# FFT_IFFT.net
KiCad netlist of a schematic drawn in Altium Designer
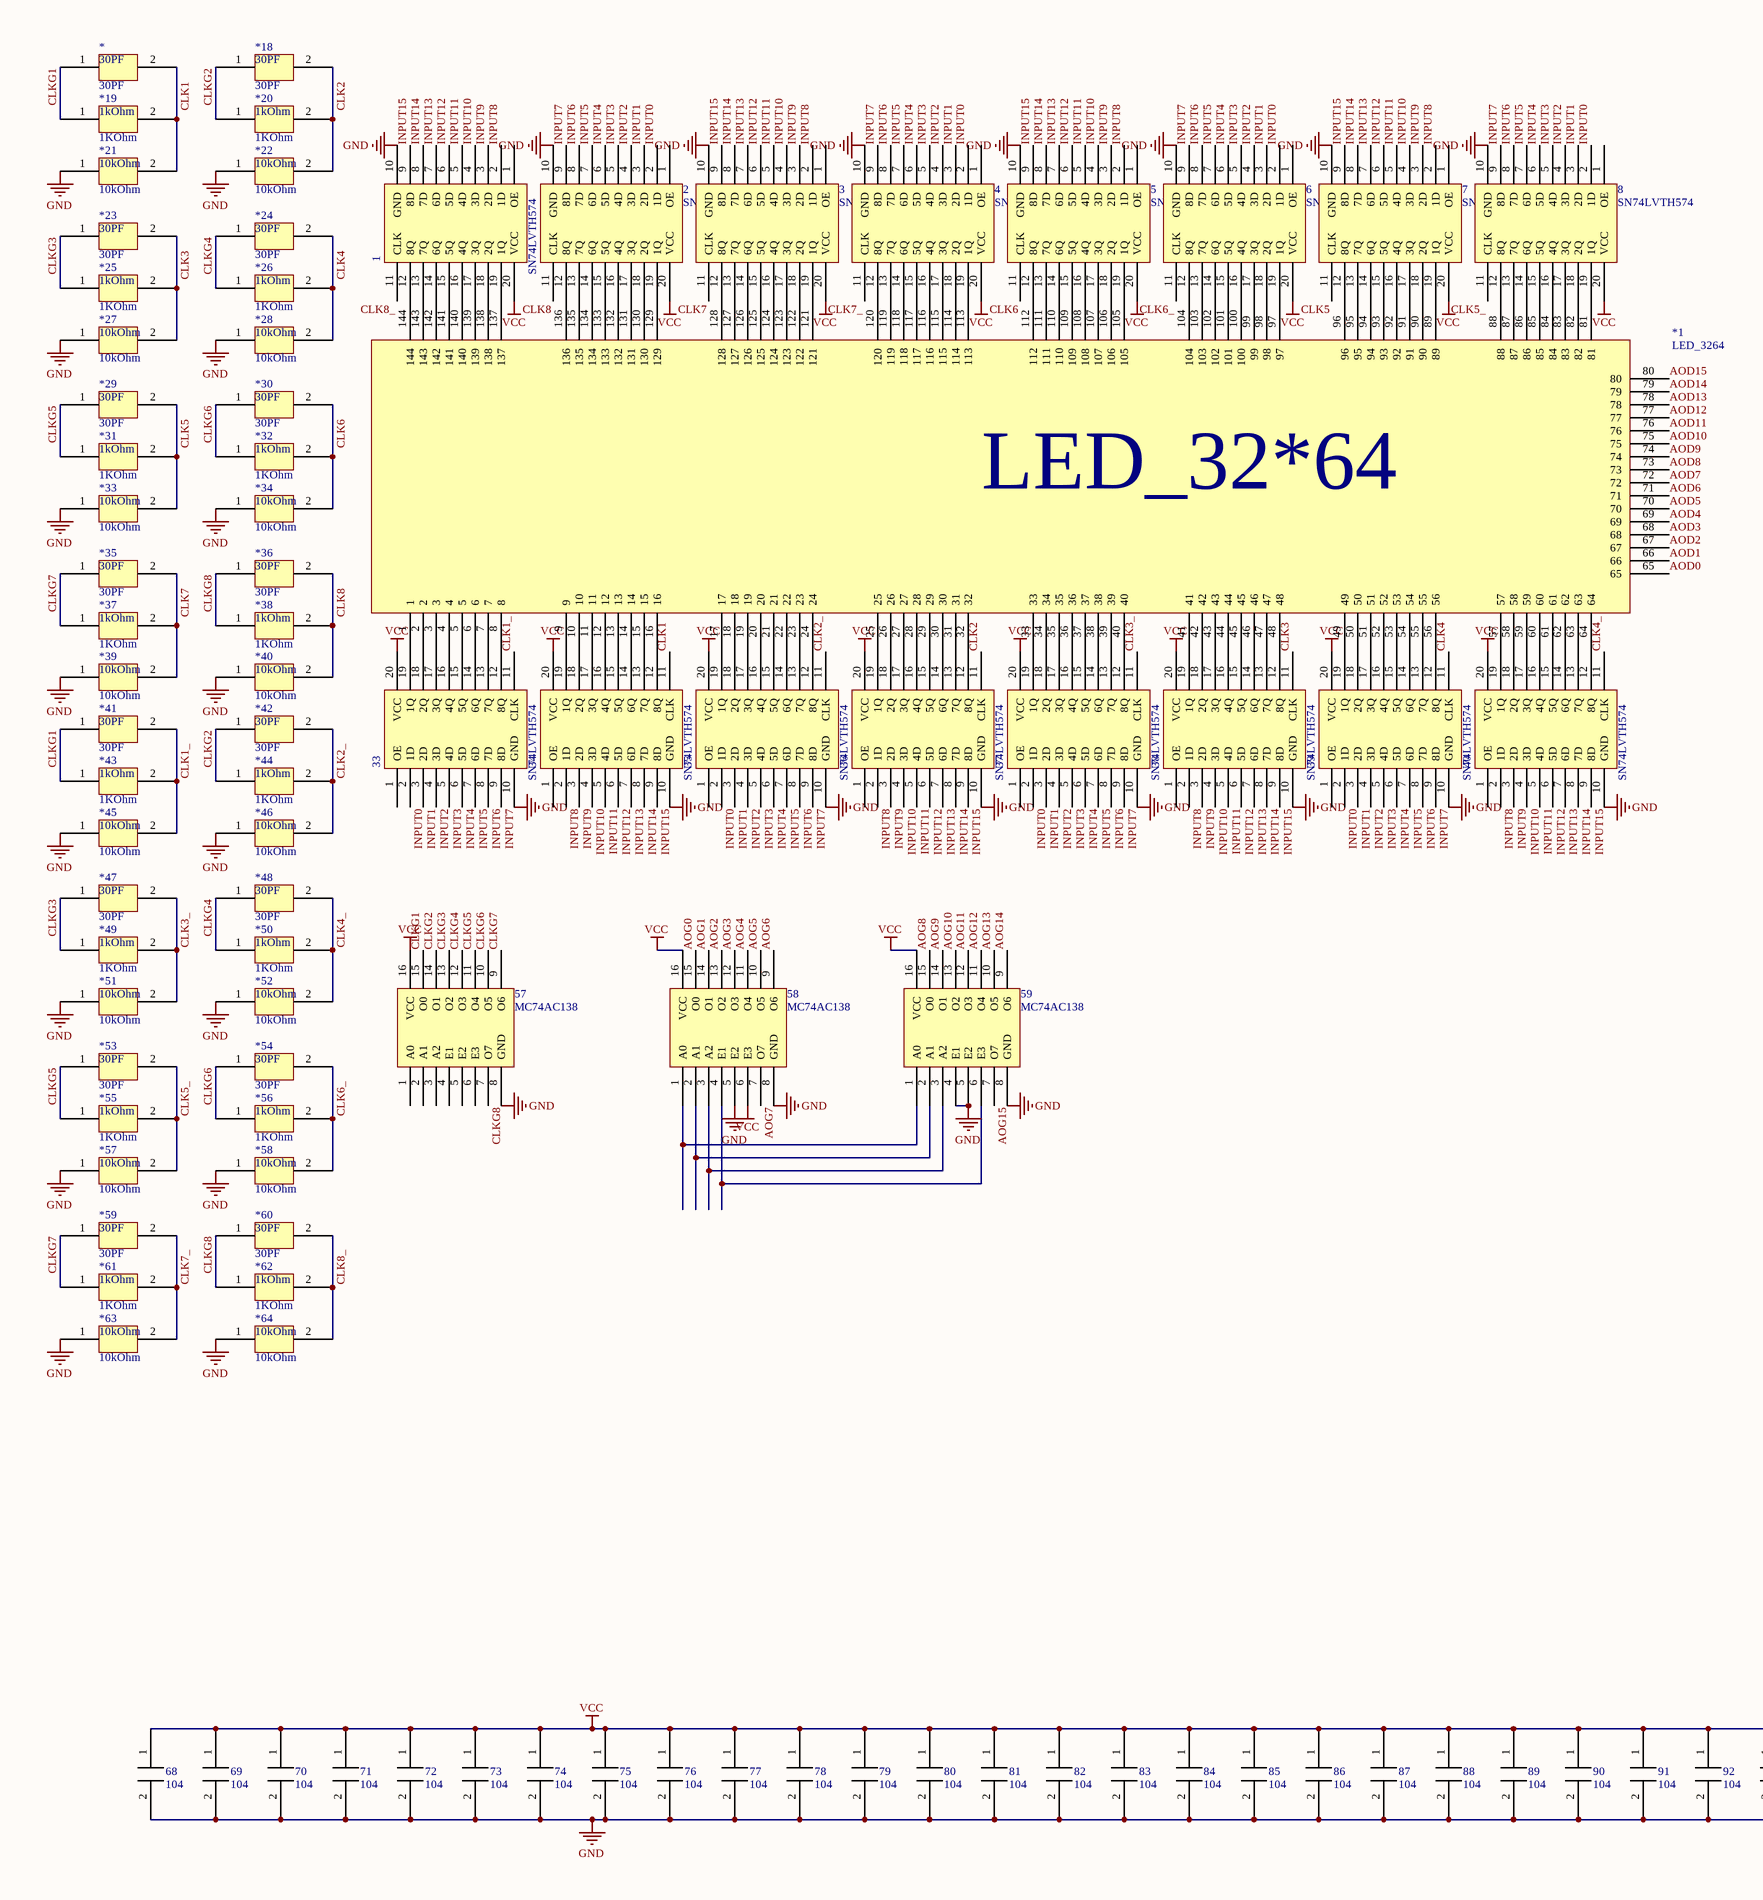
[diagram p0: FFT_IFFT.SchDoc, left]
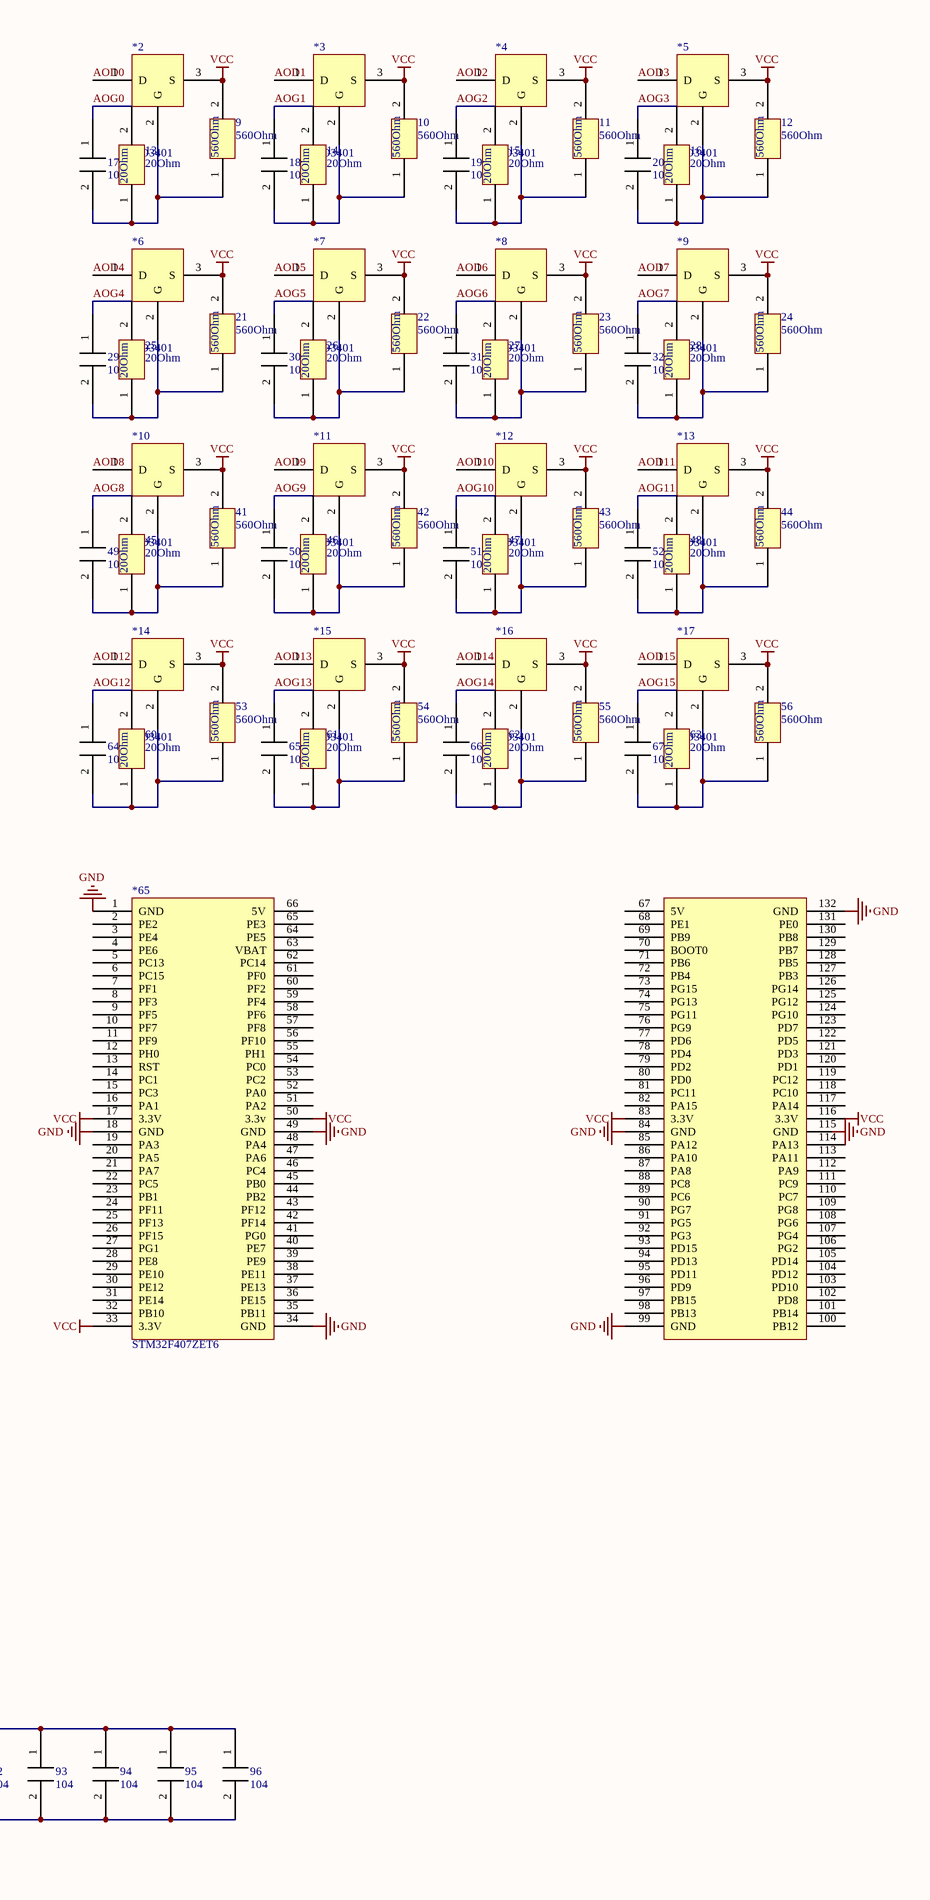
[diagram p1: FFT_IFFT.SchDoc, right]

(export (version "E")
  (design (tool "Eeschema 10.0.6"))
  (components
    (comp (ref "*") (value "30PF") (footprint "104") (libsource (lib "Schlib1") (part "30PF")))
    (comp (ref "*1") (value "LED_3264") (footprint "LED_3264") (libsource (lib "Schlib1") (part "LED_3264")))
    (comp (ref "*2") (value "AO3401") (footprint "AO3401") (libsource (lib "Schlib1") (part "AO3401")))
    (comp (ref "*3") (value "AO3401") (footprint "AO3401") (libsource (lib "Schlib1") (part "AO3401")))
    (comp (ref "*4") (value "AO3401") (footprint "AO3401") (libsource (lib "Schlib1") (part "AO3401")))
    (comp (ref "*5") (value "AO3401") (footprint "AO3401") (libsource (lib "Schlib1") (part "AO3401")))
    (comp (ref "*6") (value "AO3401") (footprint "AO3401") (libsource (lib "Schlib1") (part "AO3401")))
    (comp (ref "*7") (value "AO3401") (footprint "AO3401") (libsource (lib "Schlib1") (part "AO3401")))
    (comp (ref "*8") (value "AO3401") (footprint "AO3401") (libsource (lib "Schlib1") (part "AO3401")))
    (comp (ref "*9") (value "AO3401") (footprint "AO3401") (libsource (lib "Schlib1") (part "AO3401")))
    (comp (ref "*10") (value "AO3401") (footprint "AO3401") (libsource (lib "Schlib1") (part "AO3401")))
    (comp (ref "*11") (value "AO3401") (footprint "AO3401") (libsource (lib "Schlib1") (part "AO3401")))
    (comp (ref "*12") (value "AO3401") (footprint "AO3401") (libsource (lib "Schlib1") (part "AO3401")))
    (comp (ref "*13") (value "AO3401") (footprint "AO3401") (libsource (lib "Schlib1") (part "AO3401")))
    (comp (ref "*14") (value "AO3401") (footprint "AO3401") (libsource (lib "Schlib1") (part "AO3401")))
    (comp (ref "*15") (value "AO3401") (footprint "AO3401") (libsource (lib "Schlib1") (part "AO3401")))
    (comp (ref "*16") (value "AO3401") (footprint "AO3401") (libsource (lib "Schlib1") (part "AO3401")))
    (comp (ref "*17") (value "AO3401") (footprint "AO3401") (libsource (lib "Schlib1") (part "AO3401")))
    (comp (ref "*18") (value "30PF") (footprint "104") (libsource (lib "Schlib1") (part "30PF")))
    (comp (ref "*19") (value "1KOhm") (footprint "104") (libsource (lib "Schlib1") (part "1KOhm")))
    (comp (ref "*20") (value "1KOhm") (footprint "104") (libsource (lib "Schlib1") (part "1KOhm")))
    (comp (ref "*21") (value "10kOhm") (footprint "104") (libsource (lib "Schlib1") (part "10kOhm")))
    (comp (ref "*22") (value "10kOhm") (footprint "104") (libsource (lib "Schlib1") (part "10kOhm")))
    (comp (ref "*23") (value "30PF") (footprint "104") (libsource (lib "Schlib1") (part "30PF")))
    (comp (ref "*24") (value "30PF") (footprint "104") (libsource (lib "Schlib1") (part "30PF")))
    (comp (ref "*25") (value "1KOhm") (footprint "104") (libsource (lib "Schlib1") (part "1KOhm")))
    (comp (ref "*26") (value "1KOhm") (footprint "104") (libsource (lib "Schlib1") (part "1KOhm")))
    (comp (ref "*27") (value "10kOhm") (footprint "104") (libsource (lib "Schlib1") (part "10kOhm")))
    (comp (ref "*28") (value "10kOhm") (footprint "104") (libsource (lib "Schlib1") (part "10kOhm")))
    (comp (ref "*29") (value "30PF") (footprint "104") (libsource (lib "Schlib1") (part "30PF")))
    (comp (ref "*30") (value "30PF") (footprint "104") (libsource (lib "Schlib1") (part "30PF")))
    (comp (ref "*31") (value "1KOhm") (footprint "104") (libsource (lib "Schlib1") (part "1KOhm")))
    (comp (ref "*32") (value "1KOhm") (footprint "104") (libsource (lib "Schlib1") (part "1KOhm")))
    (comp (ref "*33") (value "10kOhm") (footprint "104") (libsource (lib "Schlib1") (part "10kOhm")))
    (comp (ref "*34") (value "10kOhm") (footprint "104") (libsource (lib "Schlib1") (part "10kOhm")))
    (comp (ref "*35") (value "30PF") (footprint "104") (libsource (lib "Schlib1") (part "30PF")))
    (comp (ref "*36") (value "30PF") (footprint "104") (libsource (lib "Schlib1") (part "30PF")))
    (comp (ref "*37") (value "1KOhm") (footprint "104") (libsource (lib "Schlib1") (part "1KOhm")))
    (comp (ref "*38") (value "1KOhm") (footprint "104") (libsource (lib "Schlib1") (part "1KOhm")))
    (comp (ref "*39") (value "10kOhm") (footprint "104") (libsource (lib "Schlib1") (part "10kOhm")))
    (comp (ref "*40") (value "10kOhm") (footprint "104") (libsource (lib "Schlib1") (part "10kOhm")))
    (comp (ref "*41") (value "30PF") (footprint "104") (libsource (lib "Schlib1") (part "30PF")))
    (comp (ref "*42") (value "30PF") (footprint "104") (libsource (lib "Schlib1") (part "30PF")))
    (comp (ref "*43") (value "1KOhm") (footprint "104") (libsource (lib "Schlib1") (part "1KOhm")))
    (comp (ref "*44") (value "1KOhm") (footprint "104") (libsource (lib "Schlib1") (part "1KOhm")))
    (comp (ref "*45") (value "10kOhm") (footprint "104") (libsource (lib "Schlib1") (part "10kOhm")))
    (comp (ref "*46") (value "10kOhm") (footprint "104") (libsource (lib "Schlib1") (part "10kOhm")))
    (comp (ref "*47") (value "30PF") (footprint "104") (libsource (lib "Schlib1") (part "30PF")))
    (comp (ref "*48") (value "30PF") (footprint "104") (libsource (lib "Schlib1") (part "30PF")))
    (comp (ref "*49") (value "1KOhm") (footprint "104") (libsource (lib "Schlib1") (part "1KOhm")))
    (comp (ref "*50") (value "1KOhm") (footprint "104") (libsource (lib "Schlib1") (part "1KOhm")))
    (comp (ref "*51") (value "10kOhm") (footprint "104") (libsource (lib "Schlib1") (part "10kOhm")))
    (comp (ref "*52") (value "10kOhm") (footprint "104") (libsource (lib "Schlib1") (part "10kOhm")))
    (comp (ref "*53") (value "30PF") (footprint "104") (libsource (lib "Schlib1") (part "30PF")))
    (comp (ref "*54") (value "30PF") (footprint "104") (libsource (lib "Schlib1") (part "30PF")))
    (comp (ref "*55") (value "1KOhm") (footprint "104") (libsource (lib "Schlib1") (part "1KOhm")))
    (comp (ref "*56") (value "1KOhm") (footprint "104") (libsource (lib "Schlib1") (part "1KOhm")))
    (comp (ref "*57") (value "10kOhm") (footprint "104") (libsource (lib "Schlib1") (part "10kOhm")))
    (comp (ref "*58") (value "10kOhm") (footprint "104") (libsource (lib "Schlib1") (part "10kOhm")))
    (comp (ref "*59") (value "30PF") (footprint "104") (libsource (lib "Schlib1") (part "30PF")))
    (comp (ref "*60") (value "30PF") (footprint "104") (libsource (lib "Schlib1") (part "30PF")))
    (comp (ref "*61") (value "1KOhm") (footprint "104") (libsource (lib "Schlib1") (part "1KOhm")))
    (comp (ref "*62") (value "1KOhm") (footprint "104") (libsource (lib "Schlib1") (part "1KOhm")))
    (comp (ref "*63") (value "10kOhm") (footprint "104") (libsource (lib "Schlib1") (part "10kOhm")))
    (comp (ref "*64") (value "10kOhm") (footprint "104") (libsource (lib "Schlib1") (part "10kOhm")))
    (comp (ref "*65")
      (value "STM32F407ZET6")
      (footprint "STM32F407ZET6")
      (libsource (lib "Schlib1") (part "STM32F407ZET6"))
    )
    (comp (ref "1")
      (value "SN74LVTH574")
      (footprint "SN74LVTH574")
      (libsource (lib "") (part "SN74LVTH574_1"))
    )
    (comp (ref "2")
      (value "SN74LVTH574")
      (footprint "SN74LVTH574")
      (libsource (lib "") (part "SN74LVTH574_1"))
    )
    (comp (ref "3")
      (value "SN74LVTH574")
      (footprint "SN74LVTH574")
      (libsource (lib "") (part "SN74LVTH574_1"))
    )
    (comp (ref "4")
      (value "SN74LVTH574")
      (footprint "SN74LVTH574")
      (libsource (lib "") (part "SN74LVTH574_1"))
    )
    (comp (ref "5")
      (value "SN74LVTH574")
      (footprint "SN74LVTH574")
      (libsource (lib "") (part "SN74LVTH574_1"))
    )
    (comp (ref "6")
      (value "SN74LVTH574")
      (footprint "SN74LVTH574")
      (libsource (lib "") (part "SN74LVTH574_1"))
    )
    (comp (ref "7")
      (value "SN74LVTH574")
      (footprint "SN74LVTH574")
      (libsource (lib "") (part "SN74LVTH574_1"))
    )
    (comp (ref "8")
      (value "SN74LVTH574")
      (footprint "SN74LVTH574")
      (libsource (lib "") (part "SN74LVTH574_1"))
    )
    (comp (ref "9") (value "560Ohm") (footprint "104") (libsource (lib "Schlib1") (part "560Ohm")))
    (comp (ref "10") (value "560Ohm") (footprint "104") (libsource (lib "Schlib1") (part "560Ohm")))
    (comp (ref "11") (value "560Ohm") (footprint "104") (libsource (lib "Schlib1") (part "560Ohm")))
    (comp (ref "12") (value "560Ohm") (footprint "104") (libsource (lib "Schlib1") (part "560Ohm")))
    (comp (ref "13") (value "20Ohm") (footprint "104") (libsource (lib "Schlib1") (part "20Ohm")))
    (comp (ref "14") (value "20Ohm") (footprint "104") (libsource (lib "Schlib1") (part "20Ohm")))
    (comp (ref "15") (value "20Ohm") (footprint "104") (libsource (lib "Schlib1") (part "20Ohm")))
    (comp (ref "16") (value "20Ohm") (footprint "104") (libsource (lib "Schlib1") (part "20Ohm")))
    (comp (ref "17") (value "104") (footprint "104") (libsource (lib "Schlib1") (part "104")))
    (comp (ref "18") (value "104") (footprint "104") (libsource (lib "Schlib1") (part "104")))
    (comp (ref "19") (value "104") (footprint "104") (libsource (lib "Schlib1") (part "104")))
    (comp (ref "20") (value "104") (footprint "104") (libsource (lib "Schlib1") (part "104")))
    (comp (ref "21") (value "560Ohm") (footprint "104") (libsource (lib "Schlib1") (part "560Ohm")))
    (comp (ref "22") (value "560Ohm") (footprint "104") (libsource (lib "Schlib1") (part "560Ohm")))
    (comp (ref "23") (value "560Ohm") (footprint "104") (libsource (lib "Schlib1") (part "560Ohm")))
    (comp (ref "24") (value "560Ohm") (footprint "104") (libsource (lib "Schlib1") (part "560Ohm")))
    (comp (ref "25") (value "20Ohm") (footprint "104") (libsource (lib "Schlib1") (part "20Ohm")))
    (comp (ref "26") (value "20Ohm") (footprint "104") (libsource (lib "Schlib1") (part "20Ohm")))
    (comp (ref "27") (value "20Ohm") (footprint "104") (libsource (lib "Schlib1") (part "20Ohm")))
    (comp (ref "28") (value "20Ohm") (footprint "104") (libsource (lib "Schlib1") (part "20Ohm")))
    (comp (ref "29") (value "104") (footprint "104") (libsource (lib "Schlib1") (part "104")))
    (comp (ref "30") (value "104") (footprint "104") (libsource (lib "Schlib1") (part "104")))
    (comp (ref "31") (value "104") (footprint "104") (libsource (lib "Schlib1") (part "104")))
    (comp (ref "32") (value "104") (footprint "104") (libsource (lib "Schlib1") (part "104")))
    (comp (ref "33")
      (value "SN74LVTH574")
      (footprint "SN74LVTH574")
      (libsource (lib "Schlib1") (part "SN74LVTH574"))
    )
    (comp (ref "34")
      (value "SN74LVTH574")
      (footprint "SN74LVTH574")
      (libsource (lib "Schlib1") (part "SN74LVTH574"))
    )
    (comp (ref "35")
      (value "SN74LVTH574")
      (footprint "SN74LVTH574")
      (libsource (lib "Schlib1") (part "SN74LVTH574"))
    )
    (comp (ref "36")
      (value "SN74LVTH574")
      (footprint "SN74LVTH574")
      (libsource (lib "Schlib1") (part "SN74LVTH574"))
    )
    (comp (ref "37")
      (value "SN74LVTH574")
      (footprint "SN74LVTH574")
      (libsource (lib "Schlib1") (part "SN74LVTH574"))
    )
    (comp (ref "38")
      (value "SN74LVTH574")
      (footprint "SN74LVTH574")
      (libsource (lib "Schlib1") (part "SN74LVTH574"))
    )
    (comp (ref "39")
      (value "SN74LVTH574")
      (footprint "SN74LVTH574")
      (libsource (lib "Schlib1") (part "SN74LVTH574"))
    )
    (comp (ref "40")
      (value "SN74LVTH574")
      (footprint "SN74LVTH574")
      (libsource (lib "Schlib1") (part "SN74LVTH574"))
    )
    (comp (ref "41") (value "560Ohm") (footprint "104") (libsource (lib "Schlib1") (part "560Ohm")))
    (comp (ref "42") (value "560Ohm") (footprint "104") (libsource (lib "Schlib1") (part "560Ohm")))
    (comp (ref "43") (value "560Ohm") (footprint "104") (libsource (lib "Schlib1") (part "560Ohm")))
    (comp (ref "44") (value "560Ohm") (footprint "104") (libsource (lib "Schlib1") (part "560Ohm")))
    (comp (ref "45") (value "20Ohm") (footprint "104") (libsource (lib "Schlib1") (part "20Ohm")))
    (comp (ref "46") (value "20Ohm") (footprint "104") (libsource (lib "Schlib1") (part "20Ohm")))
    (comp (ref "47") (value "20Ohm") (footprint "104") (libsource (lib "Schlib1") (part "20Ohm")))
    (comp (ref "48") (value "20Ohm") (footprint "104") (libsource (lib "Schlib1") (part "20Ohm")))
    (comp (ref "49") (value "104") (footprint "104") (libsource (lib "Schlib1") (part "104")))
    (comp (ref "50") (value "104") (footprint "104") (libsource (lib "Schlib1") (part "104")))
    (comp (ref "51") (value "104") (footprint "104") (libsource (lib "Schlib1") (part "104")))
    (comp (ref "52") (value "104") (footprint "104") (libsource (lib "Schlib1") (part "104")))
    (comp (ref "53") (value "560Ohm") (footprint "104") (libsource (lib "Schlib1") (part "560Ohm")))
    (comp (ref "54") (value "560Ohm") (footprint "104") (libsource (lib "Schlib1") (part "560Ohm")))
    (comp (ref "55") (value "560Ohm") (footprint "104") (libsource (lib "Schlib1") (part "560Ohm")))
    (comp (ref "56") (value "560Ohm") (footprint "104") (libsource (lib "Schlib1") (part "560Ohm")))
    (comp (ref "57")
      (value "MC74AC138")
      (footprint "MC74AC138")
      (libsource (lib "Schlib1") (part "MC74AC138"))
    )
    (comp (ref "58")
      (value "MC74AC138")
      (footprint "MC74AC138")
      (libsource (lib "Schlib1") (part "MC74AC138"))
    )
    (comp (ref "59")
      (value "MC74AC138")
      (footprint "MC74AC138")
      (libsource (lib "Schlib1") (part "MC74AC138"))
    )
    (comp (ref "60") (value "20Ohm") (footprint "104") (libsource (lib "Schlib1") (part "20Ohm")))
    (comp (ref "61") (value "20Ohm") (footprint "104") (libsource (lib "Schlib1") (part "20Ohm")))
    (comp (ref "62") (value "20Ohm") (footprint "104") (libsource (lib "Schlib1") (part "20Ohm")))
    (comp (ref "63") (value "20Ohm") (footprint "104") (libsource (lib "Schlib1") (part "20Ohm")))
    (comp (ref "64") (value "104") (footprint "104") (libsource (lib "Schlib1") (part "104")))
    (comp (ref "65") (value "104") (footprint "104") (libsource (lib "Schlib1") (part "104")))
    (comp (ref "66") (value "104") (footprint "104") (libsource (lib "Schlib1") (part "104")))
    (comp (ref "67") (value "104") (footprint "104") (libsource (lib "Schlib1") (part "104")))
    (comp (ref "68") (value "104") (footprint "104") (libsource (lib "Schlib1") (part "104")))
    (comp (ref "69") (value "104") (footprint "104") (libsource (lib "Schlib1") (part "104")))
    (comp (ref "70") (value "104") (footprint "104") (libsource (lib "Schlib1") (part "104")))
    (comp (ref "71") (value "104") (footprint "104") (libsource (lib "Schlib1") (part "104")))
    (comp (ref "72") (value "104") (footprint "104") (libsource (lib "Schlib1") (part "104")))
    (comp (ref "73") (value "104") (footprint "104") (libsource (lib "Schlib1") (part "104")))
    (comp (ref "74") (value "104") (footprint "104") (libsource (lib "Schlib1") (part "104")))
    (comp (ref "75") (value "104") (footprint "104") (libsource (lib "Schlib1") (part "104")))
    (comp (ref "76") (value "104") (footprint "104") (libsource (lib "Schlib1") (part "104")))
    (comp (ref "77") (value "104") (footprint "104") (libsource (lib "Schlib1") (part "104")))
    (comp (ref "78") (value "104") (footprint "104") (libsource (lib "Schlib1") (part "104")))
    (comp (ref "79") (value "104") (footprint "104") (libsource (lib "Schlib1") (part "104")))
    (comp (ref "80") (value "104") (footprint "104") (libsource (lib "Schlib1") (part "104")))
    (comp (ref "81") (value "104") (footprint "104") (libsource (lib "Schlib1") (part "104")))
    (comp (ref "82") (value "104") (footprint "104") (libsource (lib "Schlib1") (part "104")))
    (comp (ref "83") (value "104") (footprint "104") (libsource (lib "Schlib1") (part "104")))
    (comp (ref "84") (value "104") (footprint "104") (libsource (lib "Schlib1") (part "104")))
    (comp (ref "85") (value "104") (footprint "104") (libsource (lib "Schlib1") (part "104")))
    (comp (ref "86") (value "104") (footprint "104") (libsource (lib "Schlib1") (part "104")))
    (comp (ref "87") (value "104") (footprint "104") (libsource (lib "Schlib1") (part "104")))
    (comp (ref "88") (value "104") (footprint "104") (libsource (lib "Schlib1") (part "104")))
    (comp (ref "89") (value "104") (footprint "104") (libsource (lib "Schlib1") (part "104")))
    (comp (ref "90") (value "104") (footprint "104") (libsource (lib "Schlib1") (part "104")))
    (comp (ref "91") (value "104") (footprint "104") (libsource (lib "Schlib1") (part "104")))
    (comp (ref "92") (value "104") (footprint "104") (libsource (lib "Schlib1") (part "104")))
    (comp (ref "93") (value "104") (footprint "104") (libsource (lib "Schlib1") (part "104")))
    (comp (ref "94") (value "104") (footprint "104") (libsource (lib "Schlib1") (part "104")))
    (comp (ref "95") (value "104") (footprint "104") (libsource (lib "Schlib1") (part "104")))
    (comp (ref "96") (value "104") (footprint "104") (libsource (lib "Schlib1") (part "104")))
  )
  (nets
    (net (code "1") (name "/AOD0") (class "Default")
      (node (ref "*1") (pin "65") (pinfunction "65_65") (pintype "passive"))
      (node (ref "*2") (pin "1") (pinfunction "D_1") (pintype "passive"))
    )
    (net (code "2") (name "/AOD1") (class "Default")
      (node (ref "*1") (pin "66") (pinfunction "66_66") (pintype "passive"))
      (node (ref "*3") (pin "1") (pinfunction "D_1") (pintype "passive"))
    )
    (net (code "3") (name "/AOD2") (class "Default")
      (node (ref "*1") (pin "67") (pinfunction "67_67") (pintype "passive"))
      (node (ref "*4") (pin "1") (pinfunction "D_1") (pintype "passive"))
    )
    (net (code "4") (name "/AOD3") (class "Default")
      (node (ref "*1") (pin "68") (pinfunction "68_68") (pintype "passive"))
      (node (ref "*5") (pin "1") (pinfunction "D_1") (pintype "passive"))
    )
    (net (code "5") (name "/AOD4") (class "Default")
      (node (ref "*1") (pin "69") (pinfunction "69_69") (pintype "passive"))
      (node (ref "*6") (pin "1") (pinfunction "D_1") (pintype "passive"))
    )
    (net (code "6") (name "/AOD5") (class "Default")
      (node (ref "*1") (pin "70") (pinfunction "70_70") (pintype "passive"))
      (node (ref "*7") (pin "1") (pinfunction "D_1") (pintype "passive"))
    )
    (net (code "7") (name "/AOD6") (class "Default")
      (node (ref "*1") (pin "71") (pinfunction "71_71") (pintype "passive"))
      (node (ref "*8") (pin "1") (pinfunction "D_1") (pintype "passive"))
    )
    (net (code "8") (name "/AOD7") (class "Default")
      (node (ref "*1") (pin "72") (pinfunction "72_72") (pintype "passive"))
      (node (ref "*9") (pin "1") (pinfunction "D_1") (pintype "passive"))
    )
    (net (code "9") (name "/AOD8") (class "Default")
      (node (ref "*1") (pin "73") (pinfunction "73_73") (pintype "passive"))
      (node (ref "*10") (pin "1") (pinfunction "D_1") (pintype "passive"))
    )
    (net (code "10") (name "/AOD9") (class "Default")
      (node (ref "*1") (pin "74") (pinfunction "74_74") (pintype "passive"))
      (node (ref "*11") (pin "1") (pinfunction "D_1") (pintype "passive"))
    )
    (net (code "11") (name "/AOD10") (class "Default")
      (node (ref "*1") (pin "75") (pinfunction "75_75") (pintype "passive"))
      (node (ref "*12") (pin "1") (pinfunction "D_1") (pintype "passive"))
    )
    (net (code "12") (name "/AOD11") (class "Default")
      (node (ref "*1") (pin "76") (pinfunction "76_76") (pintype "passive"))
      (node (ref "*13") (pin "1") (pinfunction "D_1") (pintype "passive"))
    )
    (net (code "13") (name "/AOD12") (class "Default")
      (node (ref "*1") (pin "77") (pinfunction "77_77") (pintype "passive"))
      (node (ref "*14") (pin "1") (pinfunction "D_1") (pintype "passive"))
    )
    (net (code "14") (name "/AOD13") (class "Default")
      (node (ref "*1") (pin "78") (pinfunction "78_78") (pintype "passive"))
      (node (ref "*15") (pin "1") (pinfunction "D_1") (pintype "passive"))
    )
    (net (code "15") (name "/AOD14") (class "Default")
      (node (ref "*1") (pin "79") (pinfunction "79_79") (pintype "passive"))
      (node (ref "*16") (pin "1") (pinfunction "D_1") (pintype "passive"))
    )
    (net (code "16") (name "/AOD15") (class "Default")
      (node (ref "*1") (pin "80") (pinfunction "80_80") (pintype "passive"))
      (node (ref "*17") (pin "1") (pinfunction "D_1") (pintype "passive"))
    )
    (net (code "17") (name "/AOG0") (class "Default")
      (node (ref "13") (pin "2") (pintype "passive"))
      (node (ref "17") (pin "1") (pintype "passive"))
      (node (ref "58") (pin "15") (pinfunction "O0_15") (pintype "passive"))
    )
    (net (code "18") (name "/AOG1") (class "Default")
      (node (ref "14") (pin "2") (pintype "passive"))
      (node (ref "18") (pin "1") (pintype "passive"))
      (node (ref "58") (pin "14") (pinfunction "O1_14") (pintype "passive"))
    )
    (net (code "19") (name "/AOG2") (class "Default")
      (node (ref "15") (pin "2") (pintype "passive"))
      (node (ref "19") (pin "1") (pintype "passive"))
      (node (ref "58") (pin "13") (pinfunction "O2_13") (pintype "passive"))
    )
    (net (code "20") (name "/AOG3") (class "Default")
      (node (ref "16") (pin "2") (pintype "passive"))
      (node (ref "20") (pin "1") (pintype "passive"))
      (node (ref "58") (pin "12") (pinfunction "O3_12") (pintype "passive"))
    )
    (net (code "21") (name "/AOG4") (class "Default")
      (node (ref "25") (pin "2") (pintype "passive"))
      (node (ref "29") (pin "1") (pintype "passive"))
      (node (ref "58") (pin "11") (pinfunction "O4_11") (pintype "passive"))
    )
    (net (code "22") (name "/AOG5") (class "Default")
      (node (ref "26") (pin "2") (pintype "passive"))
      (node (ref "30") (pin "1") (pintype "passive"))
      (node (ref "58") (pin "10") (pinfunction "O5_10") (pintype "passive"))
    )
    (net (code "23") (name "/AOG6") (class "Default")
      (node (ref "27") (pin "2") (pintype "passive"))
      (node (ref "31") (pin "1") (pintype "passive"))
      (node (ref "58") (pin "9") (pinfunction "O6_9") (pintype "passive"))
    )
    (net (code "24") (name "/AOG7") (class "Default")
      (node (ref "28") (pin "2") (pintype "passive"))
      (node (ref "32") (pin "1") (pintype "passive"))
      (node (ref "58") (pin "7") (pinfunction "O7_7") (pintype "passive"))
    )
    (net (code "25") (name "/AOG8") (class "Default")
      (node (ref "45") (pin "2") (pintype "passive"))
      (node (ref "49") (pin "1") (pintype "passive"))
      (node (ref "59") (pin "15") (pinfunction "O0_15") (pintype "passive"))
    )
    (net (code "26") (name "/AOG9") (class "Default")
      (node (ref "46") (pin "2") (pintype "passive"))
      (node (ref "50") (pin "1") (pintype "passive"))
      (node (ref "59") (pin "14") (pinfunction "O1_14") (pintype "passive"))
    )
    (net (code "27") (name "/AOG10") (class "Default")
      (node (ref "47") (pin "2") (pintype "passive"))
      (node (ref "51") (pin "1") (pintype "passive"))
      (node (ref "59") (pin "13") (pinfunction "O2_13") (pintype "passive"))
    )
    (net (code "28") (name "/AOG11") (class "Default")
      (node (ref "48") (pin "2") (pintype "passive"))
      (node (ref "52") (pin "1") (pintype "passive"))
      (node (ref "59") (pin "12") (pinfunction "O3_12") (pintype "passive"))
    )
    (net (code "29") (name "/AOG12") (class "Default")
      (node (ref "59") (pin "11") (pinfunction "O4_11") (pintype "passive"))
      (node (ref "60") (pin "2") (pintype "passive"))
      (node (ref "64") (pin "1") (pintype "passive"))
    )
    (net (code "30") (name "/AOG13") (class "Default")
      (node (ref "59") (pin "10") (pinfunction "O5_10") (pintype "passive"))
      (node (ref "61") (pin "2") (pintype "passive"))
      (node (ref "65") (pin "1") (pintype "passive"))
    )
    (net (code "31") (name "/AOG14") (class "Default")
      (node (ref "59") (pin "9") (pinfunction "O6_9") (pintype "passive"))
      (node (ref "62") (pin "2") (pintype "passive"))
      (node (ref "66") (pin "1") (pintype "passive"))
    )
    (net (code "32") (name "/AOG15") (class "Default")
      (node (ref "59") (pin "7") (pinfunction "O7_7") (pintype "passive"))
      (node (ref "63") (pin "2") (pintype "passive"))
      (node (ref "67") (pin "1") (pintype "passive"))
    )
    (net (code "33") (name "/CLK1") (class "Default")
      (node (ref "*") (pin "2") (pintype "passive"))
      (node (ref "*19") (pin "2") (pintype "passive"))
      (node (ref "*21") (pin "2") (pintype "passive"))
      (node (ref "34") (pin "11") (pinfunction "CLK_11") (pintype "passive"))
    )
    (net (code "34") (name "/CLK1_") (class "Default")
      (node (ref "*41") (pin "2") (pintype "passive"))
      (node (ref "*43") (pin "2") (pintype "passive"))
      (node (ref "*45") (pin "2") (pintype "passive"))
      (node (ref "33") (pin "11") (pinfunction "CLK_11") (pintype "passive"))
    )
    (net (code "35") (name "/CLK2") (class "Default")
      (node (ref "*18") (pin "2") (pintype "passive"))
      (node (ref "*20") (pin "2") (pintype "passive"))
      (node (ref "*22") (pin "2") (pintype "passive"))
      (node (ref "36") (pin "11") (pinfunction "CLK_11") (pintype "passive"))
    )
    (net (code "36") (name "/CLK2_") (class "Default")
      (node (ref "*42") (pin "2") (pintype "passive"))
      (node (ref "*44") (pin "2") (pintype "passive"))
      (node (ref "*46") (pin "2") (pintype "passive"))
      (node (ref "35") (pin "11") (pinfunction "CLK_11") (pintype "passive"))
    )
    (net (code "37") (name "/CLK3") (class "Default")
      (node (ref "*23") (pin "2") (pintype "passive"))
      (node (ref "*25") (pin "2") (pintype "passive"))
      (node (ref "*27") (pin "2") (pintype "passive"))
      (node (ref "38") (pin "11") (pinfunction "CLK_11") (pintype "passive"))
    )
    (net (code "38") (name "/CLK3_") (class "Default")
      (node (ref "*47") (pin "2") (pintype "passive"))
      (node (ref "*49") (pin "2") (pintype "passive"))
      (node (ref "*51") (pin "2") (pintype "passive"))
      (node (ref "37") (pin "11") (pinfunction "CLK_11") (pintype "passive"))
    )
    (net (code "39") (name "/CLK4") (class "Default")
      (node (ref "*24") (pin "2") (pintype "passive"))
      (node (ref "*26") (pin "2") (pintype "passive"))
      (node (ref "*28") (pin "2") (pintype "passive"))
      (node (ref "39") (pin "11") (pinfunction "CLK_11") (pintype "passive"))
    )
    (net (code "40") (name "/CLK4_") (class "Default")
      (node (ref "*48") (pin "2") (pintype "passive"))
      (node (ref "*50") (pin "2") (pintype "passive"))
      (node (ref "*52") (pin "2") (pintype "passive"))
      (node (ref "40") (pin "11") (pinfunction "CLK_11") (pintype "passive"))
    )
    (net (code "41") (name "/CLK5") (class "Default")
      (node (ref "*29") (pin "2") (pintype "passive"))
      (node (ref "*31") (pin "2") (pintype "passive"))
      (node (ref "*33") (pin "2") (pintype "passive"))
      (node (ref "7") (pin "11") (pinfunction "CLK_11") (pintype "passive"))
    )
    (net (code "42") (name "/CLK5_") (class "Default")
      (node (ref "*53") (pin "2") (pintype "passive"))
      (node (ref "*55") (pin "2") (pintype "passive"))
      (node (ref "*57") (pin "2") (pintype "passive"))
      (node (ref "8") (pin "11") (pinfunction "CLK_11") (pintype "passive"))
    )
    (net (code "43") (name "/CLK6") (class "Default")
      (node (ref "*30") (pin "2") (pintype "passive"))
      (node (ref "*32") (pin "2") (pintype "passive"))
      (node (ref "*34") (pin "2") (pintype "passive"))
      (node (ref "5") (pin "11") (pinfunction "CLK_11") (pintype "passive"))
    )
    (net (code "44") (name "/CLK6_") (class "Default")
      (node (ref "*54") (pin "2") (pintype "passive"))
      (node (ref "*56") (pin "2") (pintype "passive"))
      (node (ref "*58") (pin "2") (pintype "passive"))
      (node (ref "6") (pin "11") (pinfunction "CLK_11") (pintype "passive"))
    )
    (net (code "45") (name "/CLK7") (class "Default")
      (node (ref "*35") (pin "2") (pintype "passive"))
      (node (ref "*37") (pin "2") (pintype "passive"))
      (node (ref "*39") (pin "2") (pintype "passive"))
      (node (ref "3") (pin "11") (pinfunction "CLK_11") (pintype "passive"))
    )
    (net (code "46") (name "/CLK7_") (class "Default")
      (node (ref "*59") (pin "2") (pintype "passive"))
      (node (ref "*61") (pin "2") (pintype "passive"))
      (node (ref "*63") (pin "2") (pintype "passive"))
      (node (ref "4") (pin "11") (pinfunction "CLK_11") (pintype "passive"))
    )
    (net (code "47") (name "/CLK8") (class "Default")
      (node (ref "*36") (pin "2") (pintype "passive"))
      (node (ref "*38") (pin "2") (pintype "passive"))
      (node (ref "*40") (pin "2") (pintype "passive"))
      (node (ref "2") (pin "11") (pinfunction "CLK_11") (pintype "passive"))
    )
    (net (code "48") (name "/CLK8_") (class "Default")
      (node (ref "*60") (pin "2") (pintype "passive"))
      (node (ref "*62") (pin "2") (pintype "passive"))
      (node (ref "*64") (pin "2") (pintype "passive"))
      (node (ref "1") (pin "11") (pinfunction "CLK_11") (pintype "passive"))
    )
    (net (code "49") (name "/CLKG1") (class "Default")
      (node (ref "*") (pin "1") (pintype "passive"))
      (node (ref "*19") (pin "1") (pintype "passive"))
      (node (ref "*41") (pin "1") (pintype "passive"))
      (node (ref "*43") (pin "1") (pintype "passive"))
      (node (ref "57") (pin "15") (pinfunction "O0_15") (pintype "passive"))
    )
    (net (code "50") (name "/CLKG2") (class "Default")
      (node (ref "*18") (pin "1") (pintype "passive"))
      (node (ref "*20") (pin "1") (pintype "passive"))
      (node (ref "*42") (pin "1") (pintype "passive"))
      (node (ref "*44") (pin "1") (pintype "passive"))
      (node (ref "57") (pin "14") (pinfunction "O1_14") (pintype "passive"))
    )
    (net (code "51") (name "/CLKG3") (class "Default")
      (node (ref "*23") (pin "1") (pintype "passive"))
      (node (ref "*25") (pin "1") (pintype "passive"))
      (node (ref "*47") (pin "1") (pintype "passive"))
      (node (ref "*49") (pin "1") (pintype "passive"))
      (node (ref "57") (pin "13") (pinfunction "O2_13") (pintype "passive"))
    )
    (net (code "52") (name "/CLKG4") (class "Default")
      (node (ref "*24") (pin "1") (pintype "passive"))
      (node (ref "*26") (pin "1") (pintype "passive"))
      (node (ref "*48") (pin "1") (pintype "passive"))
      (node (ref "*50") (pin "1") (pintype "passive"))
      (node (ref "57") (pin "12") (pinfunction "O3_12") (pintype "passive"))
    )
    (net (code "53") (name "/CLKG5") (class "Default")
      (node (ref "*29") (pin "1") (pintype "passive"))
      (node (ref "*31") (pin "1") (pintype "passive"))
      (node (ref "*53") (pin "1") (pintype "passive"))
      (node (ref "*55") (pin "1") (pintype "passive"))
      (node (ref "57") (pin "11") (pinfunction "O4_11") (pintype "passive"))
    )
    (net (code "54") (name "/CLKG6") (class "Default")
      (node (ref "*30") (pin "1") (pintype "passive"))
      (node (ref "*32") (pin "1") (pintype "passive"))
      (node (ref "*54") (pin "1") (pintype "passive"))
      (node (ref "*56") (pin "1") (pintype "passive"))
      (node (ref "57") (pin "10") (pinfunction "O5_10") (pintype "passive"))
    )
    (net (code "55") (name "/CLKG7") (class "Default")
      (node (ref "*35") (pin "1") (pintype "passive"))
      (node (ref "*37") (pin "1") (pintype "passive"))
      (node (ref "*59") (pin "1") (pintype "passive"))
      (node (ref "*61") (pin "1") (pintype "passive"))
      (node (ref "57") (pin "9") (pinfunction "O6_9") (pintype "passive"))
    )
    (net (code "56") (name "/CLKG8") (class "Default")
      (node (ref "*36") (pin "1") (pintype "passive"))
      (node (ref "*38") (pin "1") (pintype "passive"))
      (node (ref "*60") (pin "1") (pintype "passive"))
      (node (ref "*62") (pin "1") (pintype "passive"))
      (node (ref "57") (pin "7") (pinfunction "O7_7") (pintype "passive"))
    )
    (net (code "57") (name "/INPUT0") (class "Default")
      (node (ref "2") (pin "2") (pinfunction "1D_2") (pintype "passive"))
      (node (ref "33") (pin "2") (pinfunction "1D_2") (pintype "passive"))
      (node (ref "35") (pin "2") (pinfunction "1D_2") (pintype "passive"))
      (node (ref "37") (pin "2") (pinfunction "1D_2") (pintype "passive"))
      (node (ref "39") (pin "2") (pinfunction "1D_2") (pintype "passive"))
      (node (ref "4") (pin "2") (pinfunction "1D_2") (pintype "passive"))
      (node (ref "6") (pin "2") (pinfunction "1D_2") (pintype "passive"))
      (node (ref "8") (pin "2") (pinfunction "1D_2") (pintype "passive"))
    )
    (net (code "58") (name "/INPUT1") (class "Default")
      (node (ref "2") (pin "3") (pinfunction "2D_3") (pintype "passive"))
      (node (ref "33") (pin "3") (pinfunction "2D_3") (pintype "passive"))
      (node (ref "35") (pin "3") (pinfunction "2D_3") (pintype "passive"))
      (node (ref "37") (pin "3") (pinfunction "2D_3") (pintype "passive"))
      (node (ref "39") (pin "3") (pinfunction "2D_3") (pintype "passive"))
      (node (ref "4") (pin "3") (pinfunction "2D_3") (pintype "passive"))
      (node (ref "6") (pin "3") (pinfunction "2D_3") (pintype "passive"))
      (node (ref "8") (pin "3") (pinfunction "2D_3") (pintype "passive"))
    )
    (net (code "59") (name "/INPUT2") (class "Default")
      (node (ref "2") (pin "4") (pinfunction "3D_4") (pintype "passive"))
      (node (ref "33") (pin "4") (pinfunction "3D_4") (pintype "passive"))
      (node (ref "35") (pin "4") (pinfunction "3D_4") (pintype "passive"))
      (node (ref "37") (pin "4") (pinfunction "3D_4") (pintype "passive"))
      (node (ref "39") (pin "4") (pinfunction "3D_4") (pintype "passive"))
      (node (ref "4") (pin "4") (pinfunction "3D_4") (pintype "passive"))
      (node (ref "6") (pin "4") (pinfunction "3D_4") (pintype "passive"))
      (node (ref "8") (pin "4") (pinfunction "3D_4") (pintype "passive"))
    )
    (net (code "60") (name "/INPUT3") (class "Default")
      (node (ref "2") (pin "5") (pinfunction "4D_5") (pintype "passive"))
      (node (ref "33") (pin "5") (pinfunction "4D_5") (pintype "passive"))
      (node (ref "35") (pin "5") (pinfunction "4D_5") (pintype "passive"))
      (node (ref "37") (pin "5") (pinfunction "4D_5") (pintype "passive"))
      (node (ref "39") (pin "5") (pinfunction "4D_5") (pintype "passive"))
      (node (ref "4") (pin "5") (pinfunction "4D_5") (pintype "passive"))
      (node (ref "6") (pin "5") (pinfunction "4D_5") (pintype "passive"))
      (node (ref "8") (pin "5") (pinfunction "4D_5") (pintype "passive"))
    )
    (net (code "61") (name "/INPUT4") (class "Default")
      (node (ref "2") (pin "6") (pinfunction "5D_6") (pintype "passive"))
      (node (ref "33") (pin "6") (pinfunction "5D_6") (pintype "passive"))
      (node (ref "35") (pin "6") (pinfunction "5D_6") (pintype "passive"))
      (node (ref "37") (pin "6") (pinfunction "5D_6") (pintype "passive"))
      (node (ref "39") (pin "6") (pinfunction "5D_6") (pintype "passive"))
      (node (ref "4") (pin "6") (pinfunction "5D_6") (pintype "passive"))
      (node (ref "6") (pin "6") (pinfunction "5D_6") (pintype "passive"))
      (node (ref "8") (pin "6") (pinfunction "5D_6") (pintype "passive"))
    )
    (net (code "62") (name "/INPUT5") (class "Default")
      (node (ref "2") (pin "7") (pinfunction "6D_7") (pintype "passive"))
      (node (ref "33") (pin "7") (pinfunction "6D_7") (pintype "passive"))
      (node (ref "35") (pin "7") (pinfunction "6D_7") (pintype "passive"))
      (node (ref "37") (pin "7") (pinfunction "6D_7") (pintype "passive"))
      (node (ref "39") (pin "7") (pinfunction "6D_7") (pintype "passive"))
      (node (ref "4") (pin "7") (pinfunction "6D_7") (pintype "passive"))
      (node (ref "6") (pin "7") (pinfunction "6D_7") (pintype "passive"))
      (node (ref "8") (pin "7") (pinfunction "6D_7") (pintype "passive"))
    )
    (net (code "63") (name "/INPUT6") (class "Default")
      (node (ref "2") (pin "8") (pinfunction "7D_8") (pintype "passive"))
      (node (ref "33") (pin "8") (pinfunction "7D_8") (pintype "passive"))
      (node (ref "35") (pin "8") (pinfunction "7D_8") (pintype "passive"))
      (node (ref "37") (pin "8") (pinfunction "7D_8") (pintype "passive"))
      (node (ref "39") (pin "8") (pinfunction "7D_8") (pintype "passive"))
      (node (ref "4") (pin "8") (pinfunction "7D_8") (pintype "passive"))
      (node (ref "6") (pin "8") (pinfunction "7D_8") (pintype "passive"))
      (node (ref "8") (pin "8") (pinfunction "7D_8") (pintype "passive"))
    )
    (net (code "64") (name "/INPUT7") (class "Default")
      (node (ref "2") (pin "9") (pinfunction "8D_9") (pintype "passive"))
      (node (ref "33") (pin "9") (pinfunction "8D_9") (pintype "passive"))
      (node (ref "35") (pin "9") (pinfunction "8D_9") (pintype "passive"))
      (node (ref "37") (pin "9") (pinfunction "8D_9") (pintype "passive"))
      (node (ref "39") (pin "9") (pinfunction "8D_9") (pintype "passive"))
      (node (ref "4") (pin "9") (pinfunction "8D_9") (pintype "passive"))
      (node (ref "6") (pin "9") (pinfunction "8D_9") (pintype "passive"))
      (node (ref "8") (pin "9") (pinfunction "8D_9") (pintype "passive"))
    )
    (net (code "65") (name "/INPUT8") (class "Default")
      (node (ref "1") (pin "2") (pinfunction "1D_2") (pintype "passive"))
      (node (ref "3") (pin "2") (pinfunction "1D_2") (pintype "passive"))
      (node (ref "34") (pin "2") (pinfunction "1D_2") (pintype "passive"))
      (node (ref "36") (pin "2") (pinfunction "1D_2") (pintype "passive"))
      (node (ref "38") (pin "2") (pinfunction "1D_2") (pintype "passive"))
      (node (ref "40") (pin "2") (pinfunction "1D_2") (pintype "passive"))
      (node (ref "5") (pin "2") (pinfunction "1D_2") (pintype "passive"))
      (node (ref "7") (pin "2") (pinfunction "1D_2") (pintype "passive"))
    )
    (net (code "66") (name "/INPUT9") (class "Default")
      (node (ref "1") (pin "3") (pinfunction "2D_3") (pintype "passive"))
      (node (ref "3") (pin "3") (pinfunction "2D_3") (pintype "passive"))
      (node (ref "34") (pin "3") (pinfunction "2D_3") (pintype "passive"))
      (node (ref "36") (pin "3") (pinfunction "2D_3") (pintype "passive"))
      (node (ref "38") (pin "3") (pinfunction "2D_3") (pintype "passive"))
      (node (ref "40") (pin "3") (pinfunction "2D_3") (pintype "passive"))
      (node (ref "5") (pin "3") (pinfunction "2D_3") (pintype "passive"))
      (node (ref "7") (pin "3") (pinfunction "2D_3") (pintype "passive"))
    )
    (net (code "67") (name "/INPUT10") (class "Default")
      (node (ref "1") (pin "4") (pinfunction "3D_4") (pintype "passive"))
      (node (ref "3") (pin "4") (pinfunction "3D_4") (pintype "passive"))
      (node (ref "34") (pin "4") (pinfunction "3D_4") (pintype "passive"))
      (node (ref "36") (pin "4") (pinfunction "3D_4") (pintype "passive"))
      (node (ref "38") (pin "4") (pinfunction "3D_4") (pintype "passive"))
      (node (ref "40") (pin "4") (pinfunction "3D_4") (pintype "passive"))
      (node (ref "5") (pin "4") (pinfunction "3D_4") (pintype "passive"))
      (node (ref "7") (pin "4") (pinfunction "3D_4") (pintype "passive"))
    )
    (net (code "68") (name "/INPUT11") (class "Default")
      (node (ref "1") (pin "5") (pinfunction "4D_5") (pintype "passive"))
      (node (ref "3") (pin "5") (pinfunction "4D_5") (pintype "passive"))
      (node (ref "34") (pin "5") (pinfunction "4D_5") (pintype "passive"))
      (node (ref "36") (pin "5") (pinfunction "4D_5") (pintype "passive"))
      (node (ref "38") (pin "5") (pinfunction "4D_5") (pintype "passive"))
      (node (ref "40") (pin "5") (pinfunction "4D_5") (pintype "passive"))
      (node (ref "5") (pin "5") (pinfunction "4D_5") (pintype "passive"))
      (node (ref "7") (pin "5") (pinfunction "4D_5") (pintype "passive"))
    )
    (net (code "69") (name "/INPUT12") (class "Default")
      (node (ref "1") (pin "6") (pinfunction "5D_6") (pintype "passive"))
      (node (ref "3") (pin "6") (pinfunction "5D_6") (pintype "passive"))
      (node (ref "34") (pin "6") (pinfunction "5D_6") (pintype "passive"))
      (node (ref "36") (pin "6") (pinfunction "5D_6") (pintype "passive"))
      (node (ref "38") (pin "6") (pinfunction "5D_6") (pintype "passive"))
      (node (ref "40") (pin "6") (pinfunction "5D_6") (pintype "passive"))
      (node (ref "5") (pin "6") (pinfunction "5D_6") (pintype "passive"))
      (node (ref "7") (pin "6") (pinfunction "5D_6") (pintype "passive"))
    )
    (net (code "70") (name "/INPUT13") (class "Default")
      (node (ref "1") (pin "7") (pinfunction "6D_7") (pintype "passive"))
      (node (ref "3") (pin "7") (pinfunction "6D_7") (pintype "passive"))
      (node (ref "34") (pin "7") (pinfunction "6D_7") (pintype "passive"))
      (node (ref "36") (pin "7") (pinfunction "6D_7") (pintype "passive"))
      (node (ref "38") (pin "7") (pinfunction "6D_7") (pintype "passive"))
      (node (ref "40") (pin "7") (pinfunction "6D_7") (pintype "passive"))
      (node (ref "5") (pin "7") (pinfunction "6D_7") (pintype "passive"))
      (node (ref "7") (pin "7") (pinfunction "6D_7") (pintype "passive"))
    )
    (net (code "71") (name "/INPUT14") (class "Default")
      (node (ref "1") (pin "8") (pinfunction "7D_8") (pintype "passive"))
      (node (ref "3") (pin "8") (pinfunction "7D_8") (pintype "passive"))
      (node (ref "34") (pin "8") (pinfunction "7D_8") (pintype "passive"))
      (node (ref "36") (pin "8") (pinfunction "7D_8") (pintype "passive"))
      (node (ref "38") (pin "8") (pinfunction "7D_8") (pintype "passive"))
      (node (ref "40") (pin "8") (pinfunction "7D_8") (pintype "passive"))
      (node (ref "5") (pin "8") (pinfunction "7D_8") (pintype "passive"))
      (node (ref "7") (pin "8") (pinfunction "7D_8") (pintype "passive"))
    )
    (net (code "72") (name "/INPUT15") (class "Default")
      (node (ref "1") (pin "9") (pinfunction "8D_9") (pintype "passive"))
      (node (ref "3") (pin "9") (pinfunction "8D_9") (pintype "passive"))
      (node (ref "34") (pin "9") (pinfunction "8D_9") (pintype "passive"))
      (node (ref "36") (pin "9") (pinfunction "8D_9") (pintype "passive"))
      (node (ref "38") (pin "9") (pinfunction "8D_9") (pintype "passive"))
      (node (ref "40") (pin "9") (pinfunction "8D_9") (pintype "passive"))
      (node (ref "5") (pin "9") (pinfunction "8D_9") (pintype "passive"))
      (node (ref "7") (pin "9") (pinfunction "8D_9") (pintype "passive"))
    )
    (net (code "73") (name "GND") (class "Default")
      (node (ref "*21") (pin "1") (pintype "passive"))
      (node (ref "*22") (pin "1") (pintype "passive"))
      (node (ref "*27") (pin "1") (pintype "passive"))
      (node (ref "*28") (pin "1") (pintype "passive"))
      (node (ref "*33") (pin "1") (pintype "passive"))
      (node (ref "*34") (pin "1") (pintype "passive"))
      (node (ref "*39") (pin "1") (pintype "passive"))
      (node (ref "*40") (pin "1") (pintype "passive"))
      (node (ref "*45") (pin "1") (pintype "passive"))
      (node (ref "*46") (pin "1") (pintype "passive"))
      (node (ref "*51") (pin "1") (pintype "passive"))
      (node (ref "*52") (pin "1") (pintype "passive"))
      (node (ref "*57") (pin "1") (pintype "passive"))
      (node (ref "*58") (pin "1") (pintype "passive"))
      (node (ref "*63") (pin "1") (pintype "passive"))
      (node (ref "*64") (pin "1") (pintype "passive"))
      (node (ref "*65") (pin "1") (pinfunction "GND_1") (pintype "passive"))
      (node (ref "*65") (pin "132") (pinfunction "GND_132") (pintype "passive"))
      (node (ref "*65") (pin "18") (pinfunction "GND_18") (pintype "passive"))
      (node (ref "*65") (pin "34") (pinfunction "GND_34") (pintype "passive"))
      (node (ref "*65") (pin "49") (pinfunction "GND_49") (pintype "passive"))
      (node (ref "*65") (pin "84") (pinfunction "GND_84") (pintype "passive"))
      (node (ref "*65") (pin "99") (pinfunction "GND_99") (pintype "passive"))
      (node (ref "1") (pin "10") (pinfunction "GND_10") (pintype "passive"))
      (node (ref "2") (pin "10") (pinfunction "GND_10") (pintype "passive"))
      (node (ref "3") (pin "10") (pinfunction "GND_10") (pintype "passive"))
      (node (ref "33") (pin "10") (pinfunction "GND_10") (pintype "passive"))
      (node (ref "34") (pin "10") (pinfunction "GND_10") (pintype "passive"))
      (node (ref "35") (pin "10") (pinfunction "GND_10") (pintype "passive"))
      (node (ref "36") (pin "10") (pinfunction "GND_10") (pintype "passive"))
      (node (ref "37") (pin "10") (pinfunction "GND_10") (pintype "passive"))
      (node (ref "38") (pin "10") (pinfunction "GND_10") (pintype "passive"))
      (node (ref "39") (pin "10") (pinfunction "GND_10") (pintype "passive"))
      (node (ref "4") (pin "10") (pinfunction "GND_10") (pintype "passive"))
      (node (ref "40") (pin "10") (pinfunction "GND_10") (pintype "passive"))
      (node (ref "5") (pin "10") (pinfunction "GND_10") (pintype "passive"))
      (node (ref "57") (pin "8") (pinfunction "GND_8") (pintype "passive"))
      (node (ref "58") (pin "5") (pinfunction "E2_5") (pintype "passive"))
      (node (ref "58") (pin "8") (pinfunction "GND_8") (pintype "passive"))
      (node (ref "59") (pin "4") (pinfunction "E1_4") (pintype "passive"))
      (node (ref "59") (pin "5") (pinfunction "E2_5") (pintype "passive"))
      (node (ref "59") (pin "8") (pinfunction "GND_8") (pintype "passive"))
      (node (ref "6") (pin "10") (pinfunction "GND_10") (pintype "passive"))
      (node (ref "68") (pin "2") (pintype "passive"))
      (node (ref "69") (pin "2") (pintype "passive"))
      (node (ref "7") (pin "10") (pinfunction "GND_10") (pintype "passive"))
      (node (ref "70") (pin "2") (pintype "passive"))
      (node (ref "71") (pin "2") (pintype "passive"))
      (node (ref "72") (pin "2") (pintype "passive"))
      (node (ref "73") (pin "2") (pintype "passive"))
      (node (ref "74") (pin "2") (pintype "passive"))
      (node (ref "75") (pin "2") (pintype "passive"))
      (node (ref "76") (pin "2") (pintype "passive"))
      (node (ref "77") (pin "2") (pintype "passive"))
      (node (ref "78") (pin "2") (pintype "passive"))
      (node (ref "79") (pin "2") (pintype "passive"))
      (node (ref "8") (pin "10") (pinfunction "GND_10") (pintype "passive"))
      (node (ref "80") (pin "2") (pintype "passive"))
      (node (ref "81") (pin "2") (pintype "passive"))
      (node (ref "82") (pin "2") (pintype "passive"))
      (node (ref "83") (pin "2") (pintype "passive"))
      (node (ref "84") (pin "2") (pintype "passive"))
      (node (ref "85") (pin "2") (pintype "passive"))
      (node (ref "86") (pin "2") (pintype "passive"))
      (node (ref "87") (pin "2") (pintype "passive"))
      (node (ref "88") (pin "2") (pintype "passive"))
      (node (ref "89") (pin "2") (pintype "passive"))
      (node (ref "90") (pin "2") (pintype "passive"))
      (node (ref "91") (pin "2") (pintype "passive"))
      (node (ref "92") (pin "2") (pintype "passive"))
      (node (ref "93") (pin "2") (pintype "passive"))
      (node (ref "94") (pin "2") (pintype "passive"))
      (node (ref "95") (pin "2") (pintype "passive"))
      (node (ref "96") (pin "2") (pintype "passive"))
    )
    (net (code "74") (name "Net-(*2-G)") (class "Default")
      (node (ref "*2") (pin "2") (pinfunction "G_2") (pintype "passive"))
      (node (ref "13") (pin "1") (pintype "passive"))
      (node (ref "17") (pin "2") (pintype "passive"))
      (node (ref "9") (pin "1") (pintype "passive"))
    )
    (net (code "75") (name "Net-(*3-G)") (class "Default")
      (node (ref "*3") (pin "2") (pinfunction "G_2") (pintype "passive"))
      (node (ref "10") (pin "1") (pintype "passive"))
      (node (ref "14") (pin "1") (pintype "passive"))
      (node (ref "18") (pin "2") (pintype "passive"))
    )
    (net (code "76") (name "Net-(*4-G)") (class "Default")
      (node (ref "*4") (pin "2") (pinfunction "G_2") (pintype "passive"))
      (node (ref "11") (pin "1") (pintype "passive"))
      (node (ref "15") (pin "1") (pintype "passive"))
      (node (ref "19") (pin "2") (pintype "passive"))
    )
    (net (code "77") (name "Net-(*5-G)") (class "Default")
      (node (ref "*5") (pin "2") (pinfunction "G_2") (pintype "passive"))
      (node (ref "12") (pin "1") (pintype "passive"))
      (node (ref "16") (pin "1") (pintype "passive"))
      (node (ref "20") (pin "2") (pintype "passive"))
    )
    (net (code "78") (name "Net-(*6-G)") (class "Default")
      (node (ref "*6") (pin "2") (pinfunction "G_2") (pintype "passive"))
      (node (ref "21") (pin "1") (pintype "passive"))
      (node (ref "25") (pin "1") (pintype "passive"))
      (node (ref "29") (pin "2") (pintype "passive"))
    )
    (net (code "79") (name "Net-(*7-G)") (class "Default")
      (node (ref "*7") (pin "2") (pinfunction "G_2") (pintype "passive"))
      (node (ref "22") (pin "1") (pintype "passive"))
      (node (ref "26") (pin "1") (pintype "passive"))
      (node (ref "30") (pin "2") (pintype "passive"))
    )
    (net (code "80") (name "Net-(*8-G)") (class "Default")
      (node (ref "*8") (pin "2") (pinfunction "G_2") (pintype "passive"))
      (node (ref "23") (pin "1") (pintype "passive"))
      (node (ref "27") (pin "1") (pintype "passive"))
      (node (ref "31") (pin "2") (pintype "passive"))
    )
    (net (code "81") (name "Net-(*9-G)") (class "Default")
      (node (ref "*9") (pin "2") (pinfunction "G_2") (pintype "passive"))
      (node (ref "24") (pin "1") (pintype "passive"))
      (node (ref "28") (pin "1") (pintype "passive"))
      (node (ref "32") (pin "2") (pintype "passive"))
    )
    (net (code "82") (name "Net-(*10-G)") (class "Default")
      (node (ref "*10") (pin "2") (pinfunction "G_2") (pintype "passive"))
      (node (ref "41") (pin "1") (pintype "passive"))
      (node (ref "45") (pin "1") (pintype "passive"))
      (node (ref "49") (pin "2") (pintype "passive"))
    )
    (net (code "83") (name "Net-(*11-G)") (class "Default")
      (node (ref "*11") (pin "2") (pinfunction "G_2") (pintype "passive"))
      (node (ref "42") (pin "1") (pintype "passive"))
      (node (ref "46") (pin "1") (pintype "passive"))
      (node (ref "50") (pin "2") (pintype "passive"))
    )
    (net (code "84") (name "Net-(*12-G)") (class "Default")
      (node (ref "*12") (pin "2") (pinfunction "G_2") (pintype "passive"))
      (node (ref "43") (pin "1") (pintype "passive"))
      (node (ref "47") (pin "1") (pintype "passive"))
      (node (ref "51") (pin "2") (pintype "passive"))
    )
    (net (code "85") (name "Net-(*13-G)") (class "Default")
      (node (ref "*13") (pin "2") (pinfunction "G_2") (pintype "passive"))
      (node (ref "44") (pin "1") (pintype "passive"))
      (node (ref "48") (pin "1") (pintype "passive"))
      (node (ref "52") (pin "2") (pintype "passive"))
    )
    (net (code "86") (name "Net-(*14-G)") (class "Default")
      (node (ref "*14") (pin "2") (pinfunction "G_2") (pintype "passive"))
      (node (ref "53") (pin "1") (pintype "passive"))
      (node (ref "60") (pin "1") (pintype "passive"))
      (node (ref "64") (pin "2") (pintype "passive"))
    )
    (net (code "87") (name "Net-(*15-G)") (class "Default")
      (node (ref "*15") (pin "2") (pinfunction "G_2") (pintype "passive"))
      (node (ref "54") (pin "1") (pintype "passive"))
      (node (ref "61") (pin "1") (pintype "passive"))
      (node (ref "65") (pin "2") (pintype "passive"))
    )
    (net (code "88") (name "Net-(*16-G)") (class "Default")
      (node (ref "*16") (pin "2") (pinfunction "G_2") (pintype "passive"))
      (node (ref "55") (pin "1") (pintype "passive"))
      (node (ref "62") (pin "1") (pintype "passive"))
      (node (ref "66") (pin "2") (pintype "passive"))
    )
    (net (code "89") (name "Net-(*17-G)") (class "Default")
      (node (ref "*17") (pin "2") (pinfunction "G_2") (pintype "passive"))
      (node (ref "56") (pin "1") (pintype "passive"))
      (node (ref "63") (pin "1") (pintype "passive"))
      (node (ref "67") (pin "2") (pintype "passive"))
    )
    (net (code "90") (name "Net-(1-1Q)") (class "Default")
      (node (ref "*1") (pin "137") (pinfunction "137_137") (pintype "passive"))
      (node (ref "1") (pin "19") (pinfunction "1Q_19") (pintype "passive"))
    )
    (net (code "91") (name "Net-(1-2Q)") (class "Default")
      (node (ref "*1") (pin "138") (pinfunction "138_138") (pintype "passive"))
      (node (ref "1") (pin "18") (pinfunction "2Q_18") (pintype "passive"))
    )
    (net (code "92") (name "Net-(1-3Q)") (class "Default")
      (node (ref "*1") (pin "139") (pinfunction "139_139") (pintype "passive"))
      (node (ref "1") (pin "17") (pinfunction "3Q_17") (pintype "passive"))
    )
    (net (code "93") (name "Net-(1-4Q)") (class "Default")
      (node (ref "*1") (pin "140") (pinfunction "140_140") (pintype "passive"))
      (node (ref "1") (pin "16") (pinfunction "4Q_16") (pintype "passive"))
    )
    (net (code "94") (name "Net-(1-5Q)") (class "Default")
      (node (ref "*1") (pin "141") (pinfunction "141_141") (pintype "passive"))
      (node (ref "1") (pin "15") (pinfunction "5Q_15") (pintype "passive"))
    )
    (net (code "95") (name "Net-(1-6Q)") (class "Default")
      (node (ref "*1") (pin "142") (pinfunction "142_142") (pintype "passive"))
      (node (ref "1") (pin "14") (pinfunction "6Q_14") (pintype "passive"))
    )
    (net (code "96") (name "Net-(1-7Q)") (class "Default")
      (node (ref "*1") (pin "143") (pinfunction "143_143") (pintype "passive"))
      (node (ref "1") (pin "13") (pinfunction "7Q_13") (pintype "passive"))
    )
    (net (code "97") (name "Net-(1-8Q)") (class "Default")
      (node (ref "*1") (pin "144") (pinfunction "144_144") (pintype "passive"))
      (node (ref "1") (pin "12") (pinfunction "8Q_12") (pintype "passive"))
    )
    (net (code "98") (name "Net-(2-1Q)") (class "Default")
      (node (ref "*1") (pin "129") (pinfunction "129_129") (pintype "passive"))
      (node (ref "2") (pin "19") (pinfunction "1Q_19") (pintype "passive"))
    )
    (net (code "99") (name "Net-(2-2Q)") (class "Default")
      (node (ref "*1") (pin "130") (pinfunction "130_130") (pintype "passive"))
      (node (ref "2") (pin "18") (pinfunction "2Q_18") (pintype "passive"))
    )
    (net (code "100") (name "Net-(2-3Q)") (class "Default")
      (node (ref "*1") (pin "131") (pinfunction "131_131") (pintype "passive"))
      (node (ref "2") (pin "17") (pinfunction "3Q_17") (pintype "passive"))
    )
    (net (code "101") (name "Net-(2-4Q)") (class "Default")
      (node (ref "*1") (pin "132") (pinfunction "132_132") (pintype "passive"))
      (node (ref "2") (pin "16") (pinfunction "4Q_16") (pintype "passive"))
    )
    (net (code "102") (name "Net-(2-5Q)") (class "Default")
      (node (ref "*1") (pin "133") (pinfunction "133_133") (pintype "passive"))
      (node (ref "2") (pin "15") (pinfunction "5Q_15") (pintype "passive"))
    )
    (net (code "103") (name "Net-(2-6Q)") (class "Default")
      (node (ref "*1") (pin "134") (pinfunction "134_134") (pintype "passive"))
      (node (ref "2") (pin "14") (pinfunction "6Q_14") (pintype "passive"))
    )
    (net (code "104") (name "Net-(2-7Q)") (class "Default")
      (node (ref "*1") (pin "135") (pinfunction "135_135") (pintype "passive"))
      (node (ref "2") (pin "13") (pinfunction "7Q_13") (pintype "passive"))
    )
    (net (code "105") (name "Net-(2-8Q)") (class "Default")
      (node (ref "*1") (pin "136") (pinfunction "136_136") (pintype "passive"))
      (node (ref "2") (pin "12") (pinfunction "8Q_12") (pintype "passive"))
    )
    (net (code "106") (name "Net-(3-1Q)") (class "Default")
      (node (ref "*1") (pin "121") (pinfunction "121_121") (pintype "passive"))
      (node (ref "3") (pin "19") (pinfunction "1Q_19") (pintype "passive"))
    )
    (net (code "107") (name "Net-(3-2Q)") (class "Default")
      (node (ref "*1") (pin "122") (pinfunction "122_122") (pintype "passive"))
      (node (ref "3") (pin "18") (pinfunction "2Q_18") (pintype "passive"))
    )
    (net (code "108") (name "Net-(3-3Q)") (class "Default")
      (node (ref "*1") (pin "123") (pinfunction "123_123") (pintype "passive"))
      (node (ref "3") (pin "17") (pinfunction "3Q_17") (pintype "passive"))
    )
    (net (code "109") (name "Net-(3-4Q)") (class "Default")
      (node (ref "*1") (pin "124") (pinfunction "124_124") (pintype "passive"))
      (node (ref "3") (pin "16") (pinfunction "4Q_16") (pintype "passive"))
    )
    (net (code "110") (name "Net-(3-5Q)") (class "Default")
      (node (ref "*1") (pin "125") (pinfunction "125_125") (pintype "passive"))
      (node (ref "3") (pin "15") (pinfunction "5Q_15") (pintype "passive"))
    )
    (net (code "111") (name "Net-(3-6Q)") (class "Default")
      (node (ref "*1") (pin "126") (pinfunction "126_126") (pintype "passive"))
      (node (ref "3") (pin "14") (pinfunction "6Q_14") (pintype "passive"))
    )
    (net (code "112") (name "Net-(3-7Q)") (class "Default")
      (node (ref "*1") (pin "127") (pinfunction "127_127") (pintype "passive"))
      (node (ref "3") (pin "13") (pinfunction "7Q_13") (pintype "passive"))
    )
    (net (code "113") (name "Net-(3-8Q)") (class "Default")
      (node (ref "*1") (pin "128") (pinfunction "128_128") (pintype "passive"))
      (node (ref "3") (pin "12") (pinfunction "8Q_12") (pintype "passive"))
    )
    (net (code "114") (name "Net-(4-1Q)") (class "Default")
      (node (ref "*1") (pin "113") (pinfunction "113_113") (pintype "passive"))
      (node (ref "4") (pin "19") (pinfunction "1Q_19") (pintype "passive"))
    )
    (net (code "115") (name "Net-(4-2Q)") (class "Default")
      (node (ref "*1") (pin "114") (pinfunction "114_114") (pintype "passive"))
      (node (ref "4") (pin "18") (pinfunction "2Q_18") (pintype "passive"))
    )
    (net (code "116") (name "Net-(4-3Q)") (class "Default")
      (node (ref "*1") (pin "115") (pinfunction "115_115") (pintype "passive"))
      (node (ref "4") (pin "17") (pinfunction "3Q_17") (pintype "passive"))
    )
    (net (code "117") (name "Net-(4-4Q)") (class "Default")
      (node (ref "*1") (pin "116") (pinfunction "116_116") (pintype "passive"))
      (node (ref "4") (pin "16") (pinfunction "4Q_16") (pintype "passive"))
    )
    (net (code "118") (name "Net-(4-5Q)") (class "Default")
      (node (ref "*1") (pin "117") (pinfunction "117_117") (pintype "passive"))
      (node (ref "4") (pin "15") (pinfunction "5Q_15") (pintype "passive"))
    )
    (net (code "119") (name "Net-(4-6Q)") (class "Default")
      (node (ref "*1") (pin "118") (pinfunction "118_118") (pintype "passive"))
      (node (ref "4") (pin "14") (pinfunction "6Q_14") (pintype "passive"))
    )
    (net (code "120") (name "Net-(4-7Q)") (class "Default")
      (node (ref "*1") (pin "119") (pinfunction "119_119") (pintype "passive"))
      (node (ref "4") (pin "13") (pinfunction "7Q_13") (pintype "passive"))
    )
    (net (code "121") (name "Net-(4-8Q)") (class "Default")
      (node (ref "*1") (pin "120") (pinfunction "120_120") (pintype "passive"))
      (node (ref "4") (pin "12") (pinfunction "8Q_12") (pintype "passive"))
    )
    (net (code "122") (name "Net-(5-1Q)") (class "Default")
      (node (ref "*1") (pin "105") (pinfunction "105_105") (pintype "passive"))
      (node (ref "5") (pin "19") (pinfunction "1Q_19") (pintype "passive"))
    )
    (net (code "123") (name "Net-(5-2Q)") (class "Default")
      (node (ref "*1") (pin "106") (pinfunction "106_106") (pintype "passive"))
      (node (ref "5") (pin "18") (pinfunction "2Q_18") (pintype "passive"))
    )
    (net (code "124") (name "Net-(5-3Q)") (class "Default")
      (node (ref "*1") (pin "107") (pinfunction "107_107") (pintype "passive"))
      (node (ref "5") (pin "17") (pinfunction "3Q_17") (pintype "passive"))
    )
    (net (code "125") (name "Net-(5-4Q)") (class "Default")
      (node (ref "*1") (pin "108") (pinfunction "108_108") (pintype "passive"))
      (node (ref "5") (pin "16") (pinfunction "4Q_16") (pintype "passive"))
    )
    (net (code "126") (name "Net-(5-5Q)") (class "Default")
      (node (ref "*1") (pin "109") (pinfunction "109_109") (pintype "passive"))
      (node (ref "5") (pin "15") (pinfunction "5Q_15") (pintype "passive"))
    )
    (net (code "127") (name "Net-(5-6Q)") (class "Default")
      (node (ref "*1") (pin "110") (pinfunction "110_110") (pintype "passive"))
      (node (ref "5") (pin "14") (pinfunction "6Q_14") (pintype "passive"))
    )
    (net (code "128") (name "Net-(5-7Q)") (class "Default")
      (node (ref "*1") (pin "111") (pinfunction "111_111") (pintype "passive"))
      (node (ref "5") (pin "13") (pinfunction "7Q_13") (pintype "passive"))
    )
    (net (code "129") (name "Net-(5-8Q)") (class "Default")
      (node (ref "*1") (pin "112") (pinfunction "112_112") (pintype "passive"))
      (node (ref "5") (pin "12") (pinfunction "8Q_12") (pintype "passive"))
    )
    (net (code "130") (name "Net-(6-1Q)") (class "Default")
      (node (ref "*1") (pin "97") (pinfunction "97_97") (pintype "passive"))
      (node (ref "6") (pin "19") (pinfunction "1Q_19") (pintype "passive"))
    )
    (net (code "131") (name "Net-(6-2Q)") (class "Default")
      (node (ref "*1") (pin "98") (pinfunction "98_98") (pintype "passive"))
      (node (ref "6") (pin "18") (pinfunction "2Q_18") (pintype "passive"))
    )
    (net (code "132") (name "Net-(6-3Q)") (class "Default")
      (node (ref "*1") (pin "99") (pinfunction "99_99") (pintype "passive"))
      (node (ref "6") (pin "17") (pinfunction "3Q_17") (pintype "passive"))
    )
    (net (code "133") (name "Net-(6-4Q)") (class "Default")
      (node (ref "*1") (pin "100") (pinfunction "100_100") (pintype "passive"))
      (node (ref "6") (pin "16") (pinfunction "4Q_16") (pintype "passive"))
    )
    (net (code "134") (name "Net-(6-5Q)") (class "Default")
      (node (ref "*1") (pin "101") (pinfunction "101_101") (pintype "passive"))
      (node (ref "6") (pin "15") (pinfunction "5Q_15") (pintype "passive"))
    )
    (net (code "135") (name "Net-(6-6Q)") (class "Default")
      (node (ref "*1") (pin "102") (pinfunction "102_102") (pintype "passive"))
      (node (ref "6") (pin "14") (pinfunction "6Q_14") (pintype "passive"))
    )
    (net (code "136") (name "Net-(6-7Q)") (class "Default")
      (node (ref "*1") (pin "103") (pinfunction "103_103") (pintype "passive"))
      (node (ref "6") (pin "13") (pinfunction "7Q_13") (pintype "passive"))
    )
    (net (code "137") (name "Net-(6-8Q)") (class "Default")
      (node (ref "*1") (pin "104") (pinfunction "104_104") (pintype "passive"))
      (node (ref "6") (pin "12") (pinfunction "8Q_12") (pintype "passive"))
    )
    (net (code "138") (name "Net-(7-1Q)") (class "Default")
      (node (ref "*1") (pin "89") (pinfunction "89_89") (pintype "passive"))
      (node (ref "7") (pin "19") (pinfunction "1Q_19") (pintype "passive"))
    )
    (net (code "139") (name "Net-(7-2Q)") (class "Default")
      (node (ref "*1") (pin "90") (pinfunction "90_90") (pintype "passive"))
      (node (ref "7") (pin "18") (pinfunction "2Q_18") (pintype "passive"))
    )
    (net (code "140") (name "Net-(7-3Q)") (class "Default")
      (node (ref "*1") (pin "91") (pinfunction "91_91") (pintype "passive"))
      (node (ref "7") (pin "17") (pinfunction "3Q_17") (pintype "passive"))
    )
    (net (code "141") (name "Net-(7-4Q)") (class "Default")
      (node (ref "*1") (pin "92") (pinfunction "92_92") (pintype "passive"))
      (node (ref "7") (pin "16") (pinfunction "4Q_16") (pintype "passive"))
    )
    (net (code "142") (name "Net-(7-5Q)") (class "Default")
      (node (ref "*1") (pin "93") (pinfunction "93_93") (pintype "passive"))
      (node (ref "7") (pin "15") (pinfunction "5Q_15") (pintype "passive"))
    )
    (net (code "143") (name "Net-(7-6Q)") (class "Default")
      (node (ref "*1") (pin "94") (pinfunction "94_94") (pintype "passive"))
      (node (ref "7") (pin "14") (pinfunction "6Q_14") (pintype "passive"))
    )
    (net (code "144") (name "Net-(7-7Q)") (class "Default")
      (node (ref "*1") (pin "95") (pinfunction "95_95") (pintype "passive"))
      (node (ref "7") (pin "13") (pinfunction "7Q_13") (pintype "passive"))
    )
    (net (code "145") (name "Net-(7-8Q)") (class "Default")
      (node (ref "*1") (pin "96") (pinfunction "96_96") (pintype "passive"))
      (node (ref "7") (pin "12") (pinfunction "8Q_12") (pintype "passive"))
    )
    (net (code "146") (name "Net-(8-1Q)") (class "Default")
      (node (ref "*1") (pin "81") (pinfunction "81_81") (pintype "passive"))
      (node (ref "8") (pin "19") (pinfunction "1Q_19") (pintype "passive"))
    )
    (net (code "147") (name "Net-(8-2Q)") (class "Default")
      (node (ref "*1") (pin "82") (pinfunction "82_82") (pintype "passive"))
      (node (ref "8") (pin "18") (pinfunction "2Q_18") (pintype "passive"))
    )
    (net (code "148") (name "Net-(8-3Q)") (class "Default")
      (node (ref "*1") (pin "83") (pinfunction "83_83") (pintype "passive"))
      (node (ref "8") (pin "17") (pinfunction "3Q_17") (pintype "passive"))
    )
    (net (code "149") (name "Net-(8-4Q)") (class "Default")
      (node (ref "*1") (pin "84") (pinfunction "84_84") (pintype "passive"))
      (node (ref "8") (pin "16") (pinfunction "4Q_16") (pintype "passive"))
    )
    (net (code "150") (name "Net-(8-5Q)") (class "Default")
      (node (ref "*1") (pin "85") (pinfunction "85_85") (pintype "passive"))
      (node (ref "8") (pin "15") (pinfunction "5Q_15") (pintype "passive"))
    )
    (net (code "151") (name "Net-(8-6Q)") (class "Default")
      (node (ref "*1") (pin "86") (pinfunction "86_86") (pintype "passive"))
      (node (ref "8") (pin "14") (pinfunction "6Q_14") (pintype "passive"))
    )
    (net (code "152") (name "Net-(8-7Q)") (class "Default")
      (node (ref "*1") (pin "87") (pinfunction "87_87") (pintype "passive"))
      (node (ref "8") (pin "13") (pinfunction "7Q_13") (pintype "passive"))
    )
    (net (code "153") (name "Net-(8-8Q)") (class "Default")
      (node (ref "*1") (pin "88") (pinfunction "88_88") (pintype "passive"))
      (node (ref "8") (pin "12") (pinfunction "8Q_12") (pintype "passive"))
    )
    (net (code "154") (name "Net-(33-1Q)") (class "Default")
      (node (ref "*1") (pin "1") (pinfunction "1_1") (pintype "passive"))
      (node (ref "33") (pin "19") (pinfunction "1Q_19") (pintype "passive"))
    )
    (net (code "155") (name "Net-(33-2Q)") (class "Default")
      (node (ref "*1") (pin "2") (pinfunction "2_2") (pintype "passive"))
      (node (ref "33") (pin "18") (pinfunction "2Q_18") (pintype "passive"))
    )
    (net (code "156") (name "Net-(33-3Q)") (class "Default")
      (node (ref "*1") (pin "3") (pinfunction "3_3") (pintype "passive"))
      (node (ref "33") (pin "17") (pinfunction "3Q_17") (pintype "passive"))
    )
    (net (code "157") (name "Net-(33-4Q)") (class "Default")
      (node (ref "*1") (pin "4") (pinfunction "4_4") (pintype "passive"))
      (node (ref "33") (pin "16") (pinfunction "4Q_16") (pintype "passive"))
    )
    (net (code "158") (name "Net-(33-5Q)") (class "Default")
      (node (ref "*1") (pin "5") (pinfunction "5_5") (pintype "passive"))
      (node (ref "33") (pin "15") (pinfunction "5Q_15") (pintype "passive"))
    )
    (net (code "159") (name "Net-(33-6Q)") (class "Default")
      (node (ref "*1") (pin "6") (pinfunction "6_6") (pintype "passive"))
      (node (ref "33") (pin "14") (pinfunction "6Q_14") (pintype "passive"))
    )
    (net (code "160") (name "Net-(33-7Q)") (class "Default")
      (node (ref "*1") (pin "7") (pinfunction "7_7") (pintype "passive"))
      (node (ref "33") (pin "13") (pinfunction "7Q_13") (pintype "passive"))
    )
    (net (code "161") (name "Net-(33-8Q)") (class "Default")
      (node (ref "*1") (pin "8") (pinfunction "8_8") (pintype "passive"))
      (node (ref "33") (pin "12") (pinfunction "8Q_12") (pintype "passive"))
    )
    (net (code "162") (name "Net-(34-1Q)") (class "Default")
      (node (ref "*1") (pin "9") (pinfunction "9_9") (pintype "passive"))
      (node (ref "34") (pin "19") (pinfunction "1Q_19") (pintype "passive"))
    )
    (net (code "163") (name "Net-(34-2Q)") (class "Default")
      (node (ref "*1") (pin "10") (pinfunction "10_10") (pintype "passive"))
      (node (ref "34") (pin "18") (pinfunction "2Q_18") (pintype "passive"))
    )
    (net (code "164") (name "Net-(34-3Q)") (class "Default")
      (node (ref "*1") (pin "11") (pinfunction "11_11") (pintype "passive"))
      (node (ref "34") (pin "17") (pinfunction "3Q_17") (pintype "passive"))
    )
    (net (code "165") (name "Net-(34-4Q)") (class "Default")
      (node (ref "*1") (pin "12") (pinfunction "12_12") (pintype "passive"))
      (node (ref "34") (pin "16") (pinfunction "4Q_16") (pintype "passive"))
    )
    (net (code "166") (name "Net-(34-5Q)") (class "Default")
      (node (ref "*1") (pin "13") (pinfunction "13_13") (pintype "passive"))
      (node (ref "34") (pin "15") (pinfunction "5Q_15") (pintype "passive"))
    )
    (net (code "167") (name "Net-(34-6Q)") (class "Default")
      (node (ref "*1") (pin "14") (pinfunction "14_14") (pintype "passive"))
      (node (ref "34") (pin "14") (pinfunction "6Q_14") (pintype "passive"))
    )
    (net (code "168") (name "Net-(34-7Q)") (class "Default")
      (node (ref "*1") (pin "15") (pinfunction "15_15") (pintype "passive"))
      (node (ref "34") (pin "13") (pinfunction "7Q_13") (pintype "passive"))
    )
    (net (code "169") (name "Net-(34-8Q)") (class "Default")
      (node (ref "*1") (pin "16") (pinfunction "16_16") (pintype "passive"))
      (node (ref "34") (pin "12") (pinfunction "8Q_12") (pintype "passive"))
    )
    (net (code "170") (name "Net-(35-1Q)") (class "Default")
      (node (ref "*1") (pin "17") (pinfunction "17_17") (pintype "passive"))
      (node (ref "35") (pin "19") (pinfunction "1Q_19") (pintype "passive"))
    )
    (net (code "171") (name "Net-(35-2Q)") (class "Default")
      (node (ref "*1") (pin "18") (pinfunction "18_18") (pintype "passive"))
      (node (ref "35") (pin "18") (pinfunction "2Q_18") (pintype "passive"))
    )
    (net (code "172") (name "Net-(35-3Q)") (class "Default")
      (node (ref "*1") (pin "19") (pinfunction "19_19") (pintype "passive"))
      (node (ref "35") (pin "17") (pinfunction "3Q_17") (pintype "passive"))
    )
    (net (code "173") (name "Net-(35-4Q)") (class "Default")
      (node (ref "*1") (pin "20") (pinfunction "20_20") (pintype "passive"))
      (node (ref "35") (pin "16") (pinfunction "4Q_16") (pintype "passive"))
    )
    (net (code "174") (name "Net-(35-5Q)") (class "Default")
      (node (ref "*1") (pin "21") (pinfunction "21_21") (pintype "passive"))
      (node (ref "35") (pin "15") (pinfunction "5Q_15") (pintype "passive"))
    )
    (net (code "175") (name "Net-(35-6Q)") (class "Default")
      (node (ref "*1") (pin "22") (pinfunction "22_22") (pintype "passive"))
      (node (ref "35") (pin "14") (pinfunction "6Q_14") (pintype "passive"))
    )
    (net (code "176") (name "Net-(35-7Q)") (class "Default")
      (node (ref "*1") (pin "23") (pinfunction "23_23") (pintype "passive"))
      (node (ref "35") (pin "13") (pinfunction "7Q_13") (pintype "passive"))
    )
    (net (code "177") (name "Net-(35-8Q)") (class "Default")
      (node (ref "*1") (pin "24") (pinfunction "24_24") (pintype "passive"))
      (node (ref "35") (pin "12") (pinfunction "8Q_12") (pintype "passive"))
    )
    (net (code "178") (name "Net-(36-1Q)") (class "Default")
      (node (ref "*1") (pin "25") (pinfunction "25_25") (pintype "passive"))
      (node (ref "36") (pin "19") (pinfunction "1Q_19") (pintype "passive"))
    )
    (net (code "179") (name "Net-(36-2Q)") (class "Default")
      (node (ref "*1") (pin "26") (pinfunction "26_26") (pintype "passive"))
      (node (ref "36") (pin "18") (pinfunction "2Q_18") (pintype "passive"))
    )
    (net (code "180") (name "Net-(36-3Q)") (class "Default")
      (node (ref "*1") (pin "27") (pinfunction "27_27") (pintype "passive"))
      (node (ref "36") (pin "17") (pinfunction "3Q_17") (pintype "passive"))
    )
    (net (code "181") (name "Net-(36-4Q)") (class "Default")
      (node (ref "*1") (pin "28") (pinfunction "28_28") (pintype "passive"))
      (node (ref "36") (pin "16") (pinfunction "4Q_16") (pintype "passive"))
    )
    (net (code "182") (name "Net-(36-5Q)") (class "Default")
      (node (ref "*1") (pin "29") (pinfunction "29_29") (pintype "passive"))
      (node (ref "36") (pin "15") (pinfunction "5Q_15") (pintype "passive"))
    )
    (net (code "183") (name "Net-(36-6Q)") (class "Default")
      (node (ref "*1") (pin "30") (pinfunction "30_30") (pintype "passive"))
      (node (ref "36") (pin "14") (pinfunction "6Q_14") (pintype "passive"))
    )
    (net (code "184") (name "Net-(36-7Q)") (class "Default")
      (node (ref "*1") (pin "31") (pinfunction "31_31") (pintype "passive"))
      (node (ref "36") (pin "13") (pinfunction "7Q_13") (pintype "passive"))
    )
    (net (code "185") (name "Net-(36-8Q)") (class "Default")
      (node (ref "*1") (pin "32") (pinfunction "32_32") (pintype "passive"))
      (node (ref "36") (pin "12") (pinfunction "8Q_12") (pintype "passive"))
    )
    (net (code "186") (name "Net-(37-1Q)") (class "Default")
      (node (ref "*1") (pin "33") (pinfunction "33_33") (pintype "passive"))
      (node (ref "37") (pin "19") (pinfunction "1Q_19") (pintype "passive"))
    )
    (net (code "187") (name "Net-(37-2Q)") (class "Default")
      (node (ref "*1") (pin "34") (pinfunction "34_34") (pintype "passive"))
      (node (ref "37") (pin "18") (pinfunction "2Q_18") (pintype "passive"))
    )
    (net (code "188") (name "Net-(37-3Q)") (class "Default")
      (node (ref "*1") (pin "35") (pinfunction "35_35") (pintype "passive"))
      (node (ref "37") (pin "17") (pinfunction "3Q_17") (pintype "passive"))
    )
    (net (code "189") (name "Net-(37-4Q)") (class "Default")
      (node (ref "*1") (pin "36") (pinfunction "36_36") (pintype "passive"))
      (node (ref "37") (pin "16") (pinfunction "4Q_16") (pintype "passive"))
    )
    (net (code "190") (name "Net-(37-5Q)") (class "Default")
      (node (ref "*1") (pin "37") (pinfunction "37_37") (pintype "passive"))
      (node (ref "37") (pin "15") (pinfunction "5Q_15") (pintype "passive"))
    )
    (net (code "191") (name "Net-(37-6Q)") (class "Default")
      (node (ref "*1") (pin "38") (pinfunction "38_38") (pintype "passive"))
      (node (ref "37") (pin "14") (pinfunction "6Q_14") (pintype "passive"))
    )
    (net (code "192") (name "Net-(37-7Q)") (class "Default")
      (node (ref "*1") (pin "39") (pinfunction "39_39") (pintype "passive"))
      (node (ref "37") (pin "13") (pinfunction "7Q_13") (pintype "passive"))
    )
    (net (code "193") (name "Net-(37-8Q)") (class "Default")
      (node (ref "*1") (pin "40") (pinfunction "40_40") (pintype "passive"))
      (node (ref "37") (pin "12") (pinfunction "8Q_12") (pintype "passive"))
    )
    (net (code "194") (name "Net-(38-1Q)") (class "Default")
      (node (ref "*1") (pin "41") (pinfunction "41_41") (pintype "passive"))
      (node (ref "38") (pin "19") (pinfunction "1Q_19") (pintype "passive"))
    )
    (net (code "195") (name "Net-(38-2Q)") (class "Default")
      (node (ref "*1") (pin "42") (pinfunction "42_42") (pintype "passive"))
      (node (ref "38") (pin "18") (pinfunction "2Q_18") (pintype "passive"))
    )
    (net (code "196") (name "Net-(38-3Q)") (class "Default")
      (node (ref "*1") (pin "43") (pinfunction "43_43") (pintype "passive"))
      (node (ref "38") (pin "17") (pinfunction "3Q_17") (pintype "passive"))
    )
    (net (code "197") (name "Net-(38-4Q)") (class "Default")
      (node (ref "*1") (pin "44") (pinfunction "44_44") (pintype "passive"))
      (node (ref "38") (pin "16") (pinfunction "4Q_16") (pintype "passive"))
    )
    (net (code "198") (name "Net-(38-5Q)") (class "Default")
      (node (ref "*1") (pin "45") (pinfunction "45_45") (pintype "passive"))
      (node (ref "38") (pin "15") (pinfunction "5Q_15") (pintype "passive"))
    )
    (net (code "199") (name "Net-(38-6Q)") (class "Default")
      (node (ref "*1") (pin "46") (pinfunction "46_46") (pintype "passive"))
      (node (ref "38") (pin "14") (pinfunction "6Q_14") (pintype "passive"))
    )
    (net (code "200") (name "Net-(38-7Q)") (class "Default")
      (node (ref "*1") (pin "47") (pinfunction "47_47") (pintype "passive"))
      (node (ref "38") (pin "13") (pinfunction "7Q_13") (pintype "passive"))
    )
    (net (code "201") (name "Net-(38-8Q)") (class "Default")
      (node (ref "*1") (pin "48") (pinfunction "48_48") (pintype "passive"))
      (node (ref "38") (pin "12") (pinfunction "8Q_12") (pintype "passive"))
    )
    (net (code "202") (name "Net-(39-1Q)") (class "Default")
      (node (ref "*1") (pin "49") (pinfunction "49_49") (pintype "passive"))
      (node (ref "39") (pin "19") (pinfunction "1Q_19") (pintype "passive"))
    )
    (net (code "203") (name "Net-(39-2Q)") (class "Default")
      (node (ref "*1") (pin "50") (pinfunction "50_50") (pintype "passive"))
      (node (ref "39") (pin "18") (pinfunction "2Q_18") (pintype "passive"))
    )
    (net (code "204") (name "Net-(39-3Q)") (class "Default")
      (node (ref "*1") (pin "51") (pinfunction "51_51") (pintype "passive"))
      (node (ref "39") (pin "17") (pinfunction "3Q_17") (pintype "passive"))
    )
    (net (code "205") (name "Net-(39-4Q)") (class "Default")
      (node (ref "*1") (pin "52") (pinfunction "52_52") (pintype "passive"))
      (node (ref "39") (pin "16") (pinfunction "4Q_16") (pintype "passive"))
    )
    (net (code "206") (name "Net-(39-5Q)") (class "Default")
      (node (ref "*1") (pin "53") (pinfunction "53_53") (pintype "passive"))
      (node (ref "39") (pin "15") (pinfunction "5Q_15") (pintype "passive"))
    )
    (net (code "207") (name "Net-(39-6Q)") (class "Default")
      (node (ref "*1") (pin "54") (pinfunction "54_54") (pintype "passive"))
      (node (ref "39") (pin "14") (pinfunction "6Q_14") (pintype "passive"))
    )
    (net (code "208") (name "Net-(39-7Q)") (class "Default")
      (node (ref "*1") (pin "55") (pinfunction "55_55") (pintype "passive"))
      (node (ref "39") (pin "13") (pinfunction "7Q_13") (pintype "passive"))
    )
    (net (code "209") (name "Net-(39-8Q)") (class "Default")
      (node (ref "*1") (pin "56") (pinfunction "56_56") (pintype "passive"))
      (node (ref "39") (pin "12") (pinfunction "8Q_12") (pintype "passive"))
    )
    (net (code "210") (name "Net-(40-1Q)") (class "Default")
      (node (ref "*1") (pin "57") (pinfunction "57_57") (pintype "passive"))
      (node (ref "40") (pin "19") (pinfunction "1Q_19") (pintype "passive"))
    )
    (net (code "211") (name "Net-(40-2Q)") (class "Default")
      (node (ref "*1") (pin "58") (pinfunction "58_58") (pintype "passive"))
      (node (ref "40") (pin "18") (pinfunction "2Q_18") (pintype "passive"))
    )
    (net (code "212") (name "Net-(40-3Q)") (class "Default")
      (node (ref "*1") (pin "59") (pinfunction "59_59") (pintype "passive"))
      (node (ref "40") (pin "17") (pinfunction "3Q_17") (pintype "passive"))
    )
    (net (code "213") (name "Net-(40-4Q)") (class "Default")
      (node (ref "*1") (pin "60") (pinfunction "60_60") (pintype "passive"))
      (node (ref "40") (pin "16") (pinfunction "4Q_16") (pintype "passive"))
    )
    (net (code "214") (name "Net-(40-5Q)") (class "Default")
      (node (ref "*1") (pin "61") (pinfunction "61_61") (pintype "passive"))
      (node (ref "40") (pin "15") (pinfunction "5Q_15") (pintype "passive"))
    )
    (net (code "215") (name "Net-(40-6Q)") (class "Default")
      (node (ref "*1") (pin "62") (pinfunction "62_62") (pintype "passive"))
      (node (ref "40") (pin "14") (pinfunction "6Q_14") (pintype "passive"))
    )
    (net (code "216") (name "Net-(40-7Q)") (class "Default")
      (node (ref "*1") (pin "63") (pinfunction "63_63") (pintype "passive"))
      (node (ref "40") (pin "13") (pinfunction "7Q_13") (pintype "passive"))
    )
    (net (code "217") (name "Net-(40-8Q)") (class "Default")
      (node (ref "*1") (pin "64") (pinfunction "64_64") (pintype "passive"))
      (node (ref "40") (pin "12") (pinfunction "8Q_12") (pintype "passive"))
    )
    (net (code "218") (name "Net-(58-A0)") (class "Default")
      (node (ref "58") (pin "1") (pinfunction "A0_1") (pintype "passive"))
      (node (ref "59") (pin "1") (pinfunction "A0_1") (pintype "passive"))
    )
    (net (code "219") (name "Net-(58-A1)") (class "Default")
      (node (ref "58") (pin "2") (pinfunction "A1_2") (pintype "passive"))
      (node (ref "59") (pin "2") (pinfunction "A1_2") (pintype "passive"))
    )
    (net (code "220") (name "Net-(58-A2)") (class "Default")
      (node (ref "58") (pin "3") (pinfunction "A2_3") (pintype "passive"))
      (node (ref "59") (pin "3") (pinfunction "A2_3") (pintype "passive"))
    )
    (net (code "221") (name "Net-(58-E1)") (class "Default")
      (node (ref "58") (pin "4") (pinfunction "E1_4") (pintype "passive"))
      (node (ref "59") (pin "6") (pinfunction "E3_6") (pintype "passive"))
    )
    (net (code "222") (name "VCC") (class "Default")
      (node (ref "*10") (pin "3") (pinfunction "S_3") (pintype "passive"))
      (node (ref "*11") (pin "3") (pinfunction "S_3") (pintype "passive"))
      (node (ref "*12") (pin "3") (pinfunction "S_3") (pintype "passive"))
      (node (ref "*13") (pin "3") (pinfunction "S_3") (pintype "passive"))
      (node (ref "*14") (pin "3") (pinfunction "S_3") (pintype "passive"))
      (node (ref "*15") (pin "3") (pinfunction "S_3") (pintype "passive"))
      (node (ref "*16") (pin "3") (pinfunction "S_3") (pintype "passive"))
      (node (ref "*17") (pin "3") (pinfunction "S_3") (pintype "passive"))
      (node (ref "*2") (pin "3") (pinfunction "S_3") (pintype "passive"))
      (node (ref "*3") (pin "3") (pinfunction "S_3") (pintype "passive"))
      (node (ref "*4") (pin "3") (pinfunction "S_3") (pintype "passive"))
      (node (ref "*5") (pin "3") (pinfunction "S_3") (pintype "passive"))
      (node (ref "*6") (pin "3") (pinfunction "S_3") (pintype "passive"))
      (node (ref "*65") (pin "116") (pinfunction "3.3V_116") (pintype "passive"))
      (node (ref "*65") (pin "17") (pinfunction "3.3V_17") (pintype "passive"))
      (node (ref "*65") (pin "33") (pinfunction "3.3V_33") (pintype "passive"))
      (node (ref "*65") (pin "50") (pinfunction "3.3v_50") (pintype "passive"))
      (node (ref "*65") (pin "83") (pinfunction "3.3V_83") (pintype "passive"))
      (node (ref "*7") (pin "3") (pinfunction "S_3") (pintype "passive"))
      (node (ref "*8") (pin "3") (pinfunction "S_3") (pintype "passive"))
      (node (ref "*9") (pin "3") (pinfunction "S_3") (pintype "passive"))
      (node (ref "1") (pin "20") (pinfunction "VCC_20") (pintype "passive"))
      (node (ref "10") (pin "2") (pintype "passive"))
      (node (ref "11") (pin "2") (pintype "passive"))
      (node (ref "12") (pin "2") (pintype "passive"))
      (node (ref "2") (pin "20") (pinfunction "VCC_20") (pintype "passive"))
      (node (ref "21") (pin "2") (pintype "passive"))
      (node (ref "22") (pin "2") (pintype "passive"))
      (node (ref "23") (pin "2") (pintype "passive"))
      (node (ref "24") (pin "2") (pintype "passive"))
      (node (ref "3") (pin "20") (pinfunction "VCC_20") (pintype "passive"))
      (node (ref "33") (pin "20") (pinfunction "VCC_20") (pintype "passive"))
      (node (ref "34") (pin "20") (pinfunction "VCC_20") (pintype "passive"))
      (node (ref "35") (pin "20") (pinfunction "VCC_20") (pintype "passive"))
      (node (ref "36") (pin "20") (pinfunction "VCC_20") (pintype "passive"))
      (node (ref "37") (pin "20") (pinfunction "VCC_20") (pintype "passive"))
      (node (ref "38") (pin "20") (pinfunction "VCC_20") (pintype "passive"))
      (node (ref "39") (pin "20") (pinfunction "VCC_20") (pintype "passive"))
      (node (ref "4") (pin "20") (pinfunction "VCC_20") (pintype "passive"))
      (node (ref "40") (pin "20") (pinfunction "VCC_20") (pintype "passive"))
      (node (ref "41") (pin "2") (pintype "passive"))
      (node (ref "42") (pin "2") (pintype "passive"))
      (node (ref "43") (pin "2") (pintype "passive"))
      (node (ref "44") (pin "2") (pintype "passive"))
      (node (ref "5") (pin "20") (pinfunction "VCC_20") (pintype "passive"))
      (node (ref "53") (pin "2") (pintype "passive"))
      (node (ref "54") (pin "2") (pintype "passive"))
      (node (ref "55") (pin "2") (pintype "passive"))
      (node (ref "56") (pin "2") (pintype "passive"))
      (node (ref "57") (pin "16") (pinfunction "VCC_16") (pintype "passive"))
      (node (ref "58") (pin "16") (pinfunction "VCC_16") (pintype "passive"))
      (node (ref "58") (pin "6") (pinfunction "E3_6") (pintype "passive"))
      (node (ref "59") (pin "16") (pinfunction "VCC_16") (pintype "passive"))
      (node (ref "6") (pin "20") (pinfunction "VCC_20") (pintype "passive"))
      (node (ref "68") (pin "1") (pintype "passive"))
      (node (ref "69") (pin "1") (pintype "passive"))
      (node (ref "7") (pin "20") (pinfunction "VCC_20") (pintype "passive"))
      (node (ref "70") (pin "1") (pintype "passive"))
      (node (ref "71") (pin "1") (pintype "passive"))
      (node (ref "72") (pin "1") (pintype "passive"))
      (node (ref "73") (pin "1") (pintype "passive"))
      (node (ref "74") (pin "1") (pintype "passive"))
      (node (ref "75") (pin "1") (pintype "passive"))
      (node (ref "76") (pin "1") (pintype "passive"))
      (node (ref "77") (pin "1") (pintype "passive"))
      (node (ref "78") (pin "1") (pintype "passive"))
      (node (ref "79") (pin "1") (pintype "passive"))
      (node (ref "8") (pin "20") (pinfunction "VCC_20") (pintype "passive"))
      (node (ref "80") (pin "1") (pintype "passive"))
      (node (ref "81") (pin "1") (pintype "passive"))
      (node (ref "82") (pin "1") (pintype "passive"))
      (node (ref "83") (pin "1") (pintype "passive"))
      (node (ref "84") (pin "1") (pintype "passive"))
      (node (ref "85") (pin "1") (pintype "passive"))
      (node (ref "86") (pin "1") (pintype "passive"))
      (node (ref "87") (pin "1") (pintype "passive"))
      (node (ref "88") (pin "1") (pintype "passive"))
      (node (ref "89") (pin "1") (pintype "passive"))
      (node (ref "9") (pin "2") (pintype "passive"))
      (node (ref "90") (pin "1") (pintype "passive"))
      (node (ref "91") (pin "1") (pintype "passive"))
      (node (ref "92") (pin "1") (pintype "passive"))
      (node (ref "93") (pin "1") (pintype "passive"))
      (node (ref "94") (pin "1") (pintype "passive"))
      (node (ref "95") (pin "1") (pintype "passive"))
      (node (ref "96") (pin "1") (pintype "passive"))
    )
    (net (code "223") (name "unconnected-(*65-5V-Pad66)") (class "Default")
      (node (ref "*65") (pin "66") (pinfunction "5V_66") (pintype "passive"))
    )
    (net (code "224") (name "unconnected-(*65-5V-Pad67)") (class "Default")
      (node (ref "*65") (pin "67") (pinfunction "5V_67") (pintype "passive"))
    )
    (net (code "225") (name "unconnected-(*65-BOOT0-Pad70)") (class "Default")
      (node (ref "*65") (pin "70") (pinfunction "BOOT0_70") (pintype "passive"))
    )
    (net (code "226") (name "unconnected-(*65-GND-Pad115)") (class "Default")
      (node (ref "*65") (pin "115") (pinfunction "GND_115") (pintype "passive"))
    )
    (net (code "227") (name "unconnected-(*65-PA0-Pad52)") (class "Default")
      (node (ref "*65") (pin "52") (pinfunction "PA0_52") (pintype "passive"))
    )
    (net (code "228") (name "unconnected-(*65-PA1-Pad16)") (class "Default")
      (node (ref "*65") (pin "16") (pinfunction "PA1_16") (pintype "passive"))
    )
    (net (code "229") (name "unconnected-(*65-PA2-Pad51)") (class "Default")
      (node (ref "*65") (pin "51") (pinfunction "PA2_51") (pintype "passive"))
    )
    (net (code "230") (name "unconnected-(*65-PA3-Pad19)") (class "Default")
      (node (ref "*65") (pin "19") (pinfunction "PA3_19") (pintype "passive"))
    )
    (net (code "231") (name "unconnected-(*65-PA4-Pad48)") (class "Default")
      (node (ref "*65") (pin "48") (pinfunction "PA4_48") (pintype "passive"))
    )
    (net (code "232") (name "unconnected-(*65-PA5-Pad20)") (class "Default")
      (node (ref "*65") (pin "20") (pinfunction "PA5_20") (pintype "passive"))
    )
    (net (code "233") (name "unconnected-(*65-PA6-Pad47)") (class "Default")
      (node (ref "*65") (pin "47") (pinfunction "PA6_47") (pintype "passive"))
    )
    (net (code "234") (name "unconnected-(*65-PA7-Pad21)") (class "Default")
      (node (ref "*65") (pin "21") (pinfunction "PA7_21") (pintype "passive"))
    )
    (net (code "235") (name "unconnected-(*65-PA8-Pad87)") (class "Default")
      (node (ref "*65") (pin "87") (pinfunction "PA8_87") (pintype "passive"))
    )
    (net (code "236") (name "unconnected-(*65-PA9-Pad112)") (class "Default")
      (node (ref "*65") (pin "112") (pinfunction "PA9_112") (pintype "passive"))
    )
    (net (code "237") (name "unconnected-(*65-PA10-Pad86)") (class "Default")
      (node (ref "*65") (pin "86") (pinfunction "PA10_86") (pintype "passive"))
    )
    (net (code "238") (name "unconnected-(*65-PA11-Pad113)") (class "Default")
      (node (ref "*65") (pin "113") (pinfunction "PA11_113") (pintype "passive"))
    )
    (net (code "239") (name "unconnected-(*65-PA12-Pad85)") (class "Default")
      (node (ref "*65") (pin "85") (pinfunction "PA12_85") (pintype "passive"))
    )
    (net (code "240") (name "unconnected-(*65-PA13-Pad114)") (class "Default")
      (node (ref "*65") (pin "114") (pinfunction "PA13_114") (pintype "passive"))
    )
    (net (code "241") (name "unconnected-(*65-PA14-Pad117)") (class "Default")
      (node (ref "*65") (pin "117") (pinfunction "PA14_117") (pintype "passive"))
    )
    (net (code "242") (name "unconnected-(*65-PA15-Pad82)") (class "Default")
      (node (ref "*65") (pin "82") (pinfunction "PA15_82") (pintype "passive"))
    )
    (net (code "243") (name "unconnected-(*65-PB0-Pad45)") (class "Default")
      (node (ref "*65") (pin "45") (pinfunction "PB0_45") (pintype "passive"))
    )
    (net (code "244") (name "unconnected-(*65-PB1-Pad23)") (class "Default")
      (node (ref "*65") (pin "23") (pinfunction "PB1_23") (pintype "passive"))
    )
    (net (code "245") (name "unconnected-(*65-PB2-Pad44)") (class "Default")
      (node (ref "*65") (pin "44") (pinfunction "PB2_44") (pintype "passive"))
    )
    (net (code "246") (name "unconnected-(*65-PB3-Pad127)") (class "Default")
      (node (ref "*65") (pin "127") (pinfunction "PB3_127") (pintype "passive"))
    )
    (net (code "247") (name "unconnected-(*65-PB4-Pad72)") (class "Default")
      (node (ref "*65") (pin "72") (pinfunction "PB4_72") (pintype "passive"))
    )
    (net (code "248") (name "unconnected-(*65-PB5-Pad128)") (class "Default")
      (node (ref "*65") (pin "128") (pinfunction "PB5_128") (pintype "passive"))
    )
    (net (code "249") (name "unconnected-(*65-PB6-Pad71)") (class "Default")
      (node (ref "*65") (pin "71") (pinfunction "PB6_71") (pintype "passive"))
    )
    (net (code "250") (name "unconnected-(*65-PB7-Pad129)") (class "Default")
      (node (ref "*65") (pin "129") (pinfunction "PB7_129") (pintype "passive"))
    )
    (net (code "251") (name "unconnected-(*65-PB8-Pad130)") (class "Default")
      (node (ref "*65") (pin "130") (pinfunction "PB8_130") (pintype "passive"))
    )
    (net (code "252") (name "unconnected-(*65-PB9-Pad69)") (class "Default")
      (node (ref "*65") (pin "69") (pinfunction "PB9_69") (pintype "passive"))
    )
    (net (code "253") (name "unconnected-(*65-PB10-Pad32)") (class "Default")
      (node (ref "*65") (pin "32") (pinfunction "PB10_32") (pintype "passive"))
    )
    (net (code "254") (name "unconnected-(*65-PB11-Pad35)") (class "Default")
      (node (ref "*65") (pin "35") (pinfunction "PB11_35") (pintype "passive"))
    )
    (net (code "255") (name "unconnected-(*65-PB12-Pad100)") (class "Default")
      (node (ref "*65") (pin "100") (pinfunction "PB12_100") (pintype "passive"))
    )
    (net (code "256") (name "unconnected-(*65-PB13-Pad98)") (class "Default")
      (node (ref "*65") (pin "98") (pinfunction "PB13_98") (pintype "passive"))
    )
    (net (code "257") (name "unconnected-(*65-PB14-Pad101)") (class "Default")
      (node (ref "*65") (pin "101") (pinfunction "PB14_101") (pintype "passive"))
    )
    (net (code "258") (name "unconnected-(*65-PB15-Pad97)") (class "Default")
      (node (ref "*65") (pin "97") (pinfunction "PB15_97") (pintype "passive"))
    )
    (net (code "259") (name "unconnected-(*65-PC0-Pad54)") (class "Default")
      (node (ref "*65") (pin "54") (pinfunction "PC0_54") (pintype "passive"))
    )
    (net (code "260") (name "unconnected-(*65-PC1-Pad14)") (class "Default")
      (node (ref "*65") (pin "14") (pinfunction "PC1_14") (pintype "passive"))
    )
    (net (code "261") (name "unconnected-(*65-PC2-Pad53)") (class "Default")
      (node (ref "*65") (pin "53") (pinfunction "PC2_53") (pintype "passive"))
    )
    (net (code "262") (name "unconnected-(*65-PC3-Pad15)") (class "Default")
      (node (ref "*65") (pin "15") (pinfunction "PC3_15") (pintype "passive"))
    )
    (net (code "263") (name "unconnected-(*65-PC4-Pad46)") (class "Default")
      (node (ref "*65") (pin "46") (pinfunction "PC4_46") (pintype "passive"))
    )
    (net (code "264") (name "unconnected-(*65-PC5-Pad22)") (class "Default")
      (node (ref "*65") (pin "22") (pinfunction "PC5_22") (pintype "passive"))
    )
    (net (code "265") (name "unconnected-(*65-PC6-Pad89)") (class "Default")
      (node (ref "*65") (pin "89") (pinfunction "PC6_89") (pintype "passive"))
    )
    (net (code "266") (name "unconnected-(*65-PC7-Pad110)") (class "Default")
      (node (ref "*65") (pin "110") (pinfunction "PC7_110") (pintype "passive"))
    )
    (net (code "267") (name "unconnected-(*65-PC8-Pad88)") (class "Default")
      (node (ref "*65") (pin "88") (pinfunction "PC8_88") (pintype "passive"))
    )
    (net (code "268") (name "unconnected-(*65-PC9-Pad111)") (class "Default")
      (node (ref "*65") (pin "111") (pinfunction "PC9_111") (pintype "passive"))
    )
    (net (code "269") (name "unconnected-(*65-PC10-Pad118)") (class "Default")
      (node (ref "*65") (pin "118") (pinfunction "PC10_118") (pintype "passive"))
    )
    (net (code "270") (name "unconnected-(*65-PC11-Pad81)") (class "Default")
      (node (ref "*65") (pin "81") (pinfunction "PC11_81") (pintype "passive"))
    )
    (net (code "271") (name "unconnected-(*65-PC12-Pad119)") (class "Default")
      (node (ref "*65") (pin "119") (pinfunction "PC12_119") (pintype "passive"))
    )
    (net (code "272") (name "unconnected-(*65-PC13-Pad5)") (class "Default")
      (node (ref "*65") (pin "5") (pinfunction "PC13_5") (pintype "passive"))
    )
    (net (code "273") (name "unconnected-(*65-PC14-Pad62)") (class "Default")
      (node (ref "*65") (pin "62") (pinfunction "PC14_62") (pintype "passive"))
    )
    (net (code "274") (name "unconnected-(*65-PC15-Pad6)") (class "Default")
      (node (ref "*65") (pin "6") (pinfunction "PC15_6") (pintype "passive"))
    )
    (net (code "275") (name "unconnected-(*65-PD0-Pad80)") (class "Default")
      (node (ref "*65") (pin "80") (pinfunction "PD0_80") (pintype "passive"))
    )
    (net (code "276") (name "unconnected-(*65-PD1-Pad120)") (class "Default")
      (node (ref "*65") (pin "120") (pinfunction "PD1_120") (pintype "passive"))
    )
    (net (code "277") (name "unconnected-(*65-PD2-Pad79)") (class "Default")
      (node (ref "*65") (pin "79") (pinfunction "PD2_79") (pintype "passive"))
    )
    (net (code "278") (name "unconnected-(*65-PD3-Pad121)") (class "Default")
      (node (ref "*65") (pin "121") (pinfunction "PD3_121") (pintype "passive"))
    )
    (net (code "279") (name "unconnected-(*65-PD4-Pad78)") (class "Default")
      (node (ref "*65") (pin "78") (pinfunction "PD4_78") (pintype "passive"))
    )
    (net (code "280") (name "unconnected-(*65-PD5-Pad122)") (class "Default")
      (node (ref "*65") (pin "122") (pinfunction "PD5_122") (pintype "passive"))
    )
    (net (code "281") (name "unconnected-(*65-PD6-Pad77)") (class "Default")
      (node (ref "*65") (pin "77") (pinfunction "PD6_77") (pintype "passive"))
    )
    (net (code "282") (name "unconnected-(*65-PD7-Pad123)") (class "Default")
      (node (ref "*65") (pin "123") (pinfunction "PD7_123") (pintype "passive"))
    )
    (net (code "283") (name "unconnected-(*65-PD8-Pad102)") (class "Default")
      (node (ref "*65") (pin "102") (pinfunction "PD8_102") (pintype "passive"))
    )
    (net (code "284") (name "unconnected-(*65-PD9-Pad96)") (class "Default")
      (node (ref "*65") (pin "96") (pinfunction "PD9_96") (pintype "passive"))
    )
    (net (code "285") (name "unconnected-(*65-PD10-Pad103)") (class "Default")
      (node (ref "*65") (pin "103") (pinfunction "PD10_103") (pintype "passive"))
    )
    (net (code "286") (name "unconnected-(*65-PD11-Pad95)") (class "Default")
      (node (ref "*65") (pin "95") (pinfunction "PD11_95") (pintype "passive"))
    )
    (net (code "287") (name "unconnected-(*65-PD12-Pad104)") (class "Default")
      (node (ref "*65") (pin "104") (pinfunction "PD12_104") (pintype "passive"))
    )
    (net (code "288") (name "unconnected-(*65-PD13-Pad94)") (class "Default")
      (node (ref "*65") (pin "94") (pinfunction "PD13_94") (pintype "passive"))
    )
    (net (code "289") (name "unconnected-(*65-PD14-Pad105)") (class "Default")
      (node (ref "*65") (pin "105") (pinfunction "PD14_105") (pintype "passive"))
    )
    (net (code "290") (name "unconnected-(*65-PD15-Pad93)") (class "Default")
      (node (ref "*65") (pin "93") (pinfunction "PD15_93") (pintype "passive"))
    )
    (net (code "291") (name "unconnected-(*65-PE0-Pad131)") (class "Default")
      (node (ref "*65") (pin "131") (pinfunction "PE0_131") (pintype "passive"))
    )
    (net (code "292") (name "unconnected-(*65-PE1-Pad68)") (class "Default")
      (node (ref "*65") (pin "68") (pinfunction "PE1_68") (pintype "passive"))
    )
    (net (code "293") (name "unconnected-(*65-PE2-Pad2)") (class "Default")
      (node (ref "*65") (pin "2") (pinfunction "PE2_2") (pintype "passive"))
    )
    (net (code "294") (name "unconnected-(*65-PE3-Pad65)") (class "Default")
      (node (ref "*65") (pin "65") (pinfunction "PE3_65") (pintype "passive"))
    )
    (net (code "295") (name "unconnected-(*65-PE4-Pad3)") (class "Default")
      (node (ref "*65") (pin "3") (pinfunction "PE4_3") (pintype "passive"))
    )
    (net (code "296") (name "unconnected-(*65-PE5-Pad64)") (class "Default")
      (node (ref "*65") (pin "64") (pinfunction "PE5_64") (pintype "passive"))
    )
    (net (code "297") (name "unconnected-(*65-PE6-Pad4)") (class "Default")
      (node (ref "*65") (pin "4") (pinfunction "PE6_4") (pintype "passive"))
    )
    (net (code "298") (name "unconnected-(*65-PE7-Pad40)") (class "Default")
      (node (ref "*65") (pin "40") (pinfunction "PE7_40") (pintype "passive"))
    )
    (net (code "299") (name "unconnected-(*65-PE8-Pad28)") (class "Default")
      (node (ref "*65") (pin "28") (pinfunction "PE8_28") (pintype "passive"))
    )
    (net (code "300") (name "unconnected-(*65-PE9-Pad39)") (class "Default")
      (node (ref "*65") (pin "39") (pinfunction "PE9_39") (pintype "passive"))
    )
    (net (code "301") (name "unconnected-(*65-PE10-Pad29)") (class "Default")
      (node (ref "*65") (pin "29") (pinfunction "PE10_29") (pintype "passive"))
    )
    (net (code "302") (name "unconnected-(*65-PE11-Pad38)") (class "Default")
      (node (ref "*65") (pin "38") (pinfunction "PE11_38") (pintype "passive"))
    )
    (net (code "303") (name "unconnected-(*65-PE12-Pad30)") (class "Default")
      (node (ref "*65") (pin "30") (pinfunction "PE12_30") (pintype "passive"))
    )
    (net (code "304") (name "unconnected-(*65-PE13-Pad37)") (class "Default")
      (node (ref "*65") (pin "37") (pinfunction "PE13_37") (pintype "passive"))
    )
    (net (code "305") (name "unconnected-(*65-PE14-Pad31)") (class "Default")
      (node (ref "*65") (pin "31") (pinfunction "PE14_31") (pintype "passive"))
    )
    (net (code "306") (name "unconnected-(*65-PE15-Pad36)") (class "Default")
      (node (ref "*65") (pin "36") (pinfunction "PE15_36") (pintype "passive"))
    )
    (net (code "307") (name "unconnected-(*65-PF0-Pad61)") (class "Default")
      (node (ref "*65") (pin "61") (pinfunction "PF0_61") (pintype "passive"))
    )
    (net (code "308") (name "unconnected-(*65-PF1-Pad7)") (class "Default")
      (node (ref "*65") (pin "7") (pinfunction "PF1_7") (pintype "passive"))
    )
    (net (code "309") (name "unconnected-(*65-PF2-Pad60)") (class "Default")
      (node (ref "*65") (pin "60") (pinfunction "PF2_60") (pintype "passive"))
    )
    (net (code "310") (name "unconnected-(*65-PF3-Pad8)") (class "Default")
      (node (ref "*65") (pin "8") (pinfunction "PF3_8") (pintype "passive"))
    )
    (net (code "311") (name "unconnected-(*65-PF4-Pad59)") (class "Default")
      (node (ref "*65") (pin "59") (pinfunction "PF4_59") (pintype "passive"))
    )
    (net (code "312") (name "unconnected-(*65-PF5-Pad9)") (class "Default")
      (node (ref "*65") (pin "9") (pinfunction "PF5_9") (pintype "passive"))
    )
    (net (code "313") (name "unconnected-(*65-PF6-Pad58)") (class "Default")
      (node (ref "*65") (pin "58") (pinfunction "PF6_58") (pintype "passive"))
    )
    (net (code "314") (name "unconnected-(*65-PF7-Pad10)") (class "Default")
      (node (ref "*65") (pin "10") (pinfunction "PF7_10") (pintype "passive"))
    )
    (net (code "315") (name "unconnected-(*65-PF8-Pad57)") (class "Default")
      (node (ref "*65") (pin "57") (pinfunction "PF8_57") (pintype "passive"))
    )
    (net (code "316") (name "unconnected-(*65-PF9-Pad11)") (class "Default")
      (node (ref "*65") (pin "11") (pinfunction "PF9_11") (pintype "passive"))
    )
    (net (code "317") (name "unconnected-(*65-PF10-Pad56)") (class "Default")
      (node (ref "*65") (pin "56") (pinfunction "PF10_56") (pintype "passive"))
    )
    (net (code "318") (name "unconnected-(*65-PF11-Pad24)") (class "Default")
      (node (ref "*65") (pin "24") (pinfunction "PF11_24") (pintype "passive"))
    )
    (net (code "319") (name "unconnected-(*65-PF12-Pad43)") (class "Default")
      (node (ref "*65") (pin "43") (pinfunction "PF12_43") (pintype "passive"))
    )
    (net (code "320") (name "unconnected-(*65-PF13-Pad25)") (class "Default")
      (node (ref "*65") (pin "25") (pinfunction "PF13_25") (pintype "passive"))
    )
    (net (code "321") (name "unconnected-(*65-PF14-Pad42)") (class "Default")
      (node (ref "*65") (pin "42") (pinfunction "PF14_42") (pintype "passive"))
    )
    (net (code "322") (name "unconnected-(*65-PF15-Pad26)") (class "Default")
      (node (ref "*65") (pin "26") (pinfunction "PF15_26") (pintype "passive"))
    )
    (net (code "323") (name "unconnected-(*65-PG0-Pad41)") (class "Default")
      (node (ref "*65") (pin "41") (pinfunction "PG0_41") (pintype "passive"))
    )
    (net (code "324") (name "unconnected-(*65-PG1-Pad27)") (class "Default")
      (node (ref "*65") (pin "27") (pinfunction "PG1_27") (pintype "passive"))
    )
    (net (code "325") (name "unconnected-(*65-PG2-Pad106)") (class "Default")
      (node (ref "*65") (pin "106") (pinfunction "PG2_106") (pintype "passive"))
    )
    (net (code "326") (name "unconnected-(*65-PG3-Pad92)") (class "Default")
      (node (ref "*65") (pin "92") (pinfunction "PG3_92") (pintype "passive"))
    )
    (net (code "327") (name "unconnected-(*65-PG4-Pad107)") (class "Default")
      (node (ref "*65") (pin "107") (pinfunction "PG4_107") (pintype "passive"))
    )
    (net (code "328") (name "unconnected-(*65-PG5-Pad91)") (class "Default")
      (node (ref "*65") (pin "91") (pinfunction "PG5_91") (pintype "passive"))
    )
    (net (code "329") (name "unconnected-(*65-PG6-Pad108)") (class "Default")
      (node (ref "*65") (pin "108") (pinfunction "PG6_108") (pintype "passive"))
    )
    (net (code "330") (name "unconnected-(*65-PG7-Pad90)") (class "Default")
      (node (ref "*65") (pin "90") (pinfunction "PG7_90") (pintype "passive"))
    )
    (net (code "331") (name "unconnected-(*65-PG8-Pad109)") (class "Default")
      (node (ref "*65") (pin "109") (pinfunction "PG8_109") (pintype "passive"))
    )
    (net (code "332") (name "unconnected-(*65-PG9-Pad76)") (class "Default")
      (node (ref "*65") (pin "76") (pinfunction "PG9_76") (pintype "passive"))
    )
    (net (code "333") (name "unconnected-(*65-PG10-Pad124)") (class "Default")
      (node (ref "*65") (pin "124") (pinfunction "PG10_124") (pintype "passive"))
    )
    (net (code "334") (name "unconnected-(*65-PG11-Pad75)") (class "Default")
      (node (ref "*65") (pin "75") (pinfunction "PG11_75") (pintype "passive"))
    )
    (net (code "335") (name "unconnected-(*65-PG12-Pad125)") (class "Default")
      (node (ref "*65") (pin "125") (pinfunction "PG12_125") (pintype "passive"))
    )
    (net (code "336") (name "unconnected-(*65-PG13-Pad74)") (class "Default")
      (node (ref "*65") (pin "74") (pinfunction "PG13_74") (pintype "passive"))
    )
    (net (code "337") (name "unconnected-(*65-PG14-Pad126)") (class "Default")
      (node (ref "*65") (pin "126") (pinfunction "PG14_126") (pintype "passive"))
    )
    (net (code "338") (name "unconnected-(*65-PG15-Pad73)") (class "Default")
      (node (ref "*65") (pin "73") (pinfunction "PG15_73") (pintype "passive"))
    )
    (net (code "339") (name "unconnected-(*65-PH0-Pad12)") (class "Default")
      (node (ref "*65") (pin "12") (pinfunction "PH0_12") (pintype "passive"))
    )
    (net (code "340") (name "unconnected-(*65-PH1-Pad55)") (class "Default")
      (node (ref "*65") (pin "55") (pinfunction "PH1_55") (pintype "passive"))
    )
    (net (code "341") (name "unconnected-(*65-RST-Pad13)") (class "Default")
      (node (ref "*65") (pin "13") (pinfunction "RST_13") (pintype "passive"))
    )
    (net (code "342") (name "unconnected-(*65-VBAT-Pad63)") (class "Default")
      (node (ref "*65") (pin "63") (pinfunction "VBAT_63") (pintype "passive"))
    )
    (net (code "343") (name "unconnected-(1-OE-Pad1)") (class "Default")
      (node (ref "1") (pin "1") (pinfunction "OE_1") (pintype "passive"))
    )
    (net (code "344") (name "unconnected-(2-OE-Pad1)") (class "Default")
      (node (ref "2") (pin "1") (pinfunction "OE_1") (pintype "passive"))
    )
    (net (code "345") (name "unconnected-(3-OE-Pad1)") (class "Default")
      (node (ref "3") (pin "1") (pinfunction "OE_1") (pintype "passive"))
    )
    (net (code "346") (name "unconnected-(4-OE-Pad1)") (class "Default")
      (node (ref "4") (pin "1") (pinfunction "OE_1") (pintype "passive"))
    )
    (net (code "347") (name "unconnected-(5-OE-Pad1)") (class "Default")
      (node (ref "5") (pin "1") (pinfunction "OE_1") (pintype "passive"))
    )
    (net (code "348") (name "unconnected-(6-OE-Pad1)") (class "Default")
      (node (ref "6") (pin "1") (pinfunction "OE_1") (pintype "passive"))
    )
    (net (code "349") (name "unconnected-(7-OE-Pad1)") (class "Default")
      (node (ref "7") (pin "1") (pinfunction "OE_1") (pintype "passive"))
    )
    (net (code "350") (name "unconnected-(8-OE-Pad1)") (class "Default")
      (node (ref "8") (pin "1") (pinfunction "OE_1") (pintype "passive"))
    )
    (net (code "351") (name "unconnected-(33-OE-Pad1)") (class "Default")
      (node (ref "33") (pin "1") (pinfunction "OE_1") (pintype "passive"))
    )
    (net (code "352") (name "unconnected-(34-OE-Pad1)") (class "Default")
      (node (ref "34") (pin "1") (pinfunction "OE_1") (pintype "passive"))
    )
    (net (code "353") (name "unconnected-(35-OE-Pad1)") (class "Default")
      (node (ref "35") (pin "1") (pinfunction "OE_1") (pintype "passive"))
    )
    (net (code "354") (name "unconnected-(36-OE-Pad1)") (class "Default")
      (node (ref "36") (pin "1") (pinfunction "OE_1") (pintype "passive"))
    )
    (net (code "355") (name "unconnected-(37-OE-Pad1)") (class "Default")
      (node (ref "37") (pin "1") (pinfunction "OE_1") (pintype "passive"))
    )
    (net (code "356") (name "unconnected-(38-OE-Pad1)") (class "Default")
      (node (ref "38") (pin "1") (pinfunction "OE_1") (pintype "passive"))
    )
    (net (code "357") (name "unconnected-(39-OE-Pad1)") (class "Default")
      (node (ref "39") (pin "1") (pinfunction "OE_1") (pintype "passive"))
    )
    (net (code "358") (name "unconnected-(40-OE-Pad1)") (class "Default")
      (node (ref "40") (pin "1") (pinfunction "OE_1") (pintype "passive"))
    )
    (net (code "359") (name "unconnected-(57-A0-Pad1)") (class "Default")
      (node (ref "57") (pin "1") (pinfunction "A0_1") (pintype "passive"))
    )
    (net (code "360") (name "unconnected-(57-A1-Pad2)") (class "Default")
      (node (ref "57") (pin "2") (pinfunction "A1_2") (pintype "passive"))
    )
    (net (code "361") (name "unconnected-(57-A2-Pad3)") (class "Default")
      (node (ref "57") (pin "3") (pinfunction "A2_3") (pintype "passive"))
    )
    (net (code "362") (name "unconnected-(57-E1-Pad4)") (class "Default")
      (node (ref "57") (pin "4") (pinfunction "E1_4") (pintype "passive"))
    )
    (net (code "363") (name "unconnected-(57-E2-Pad5)") (class "Default")
      (node (ref "57") (pin "5") (pinfunction "E2_5") (pintype "passive"))
    )
    (net (code "364") (name "unconnected-(57-E3-Pad6)") (class "Default")
      (node (ref "57") (pin "6") (pinfunction "E3_6") (pintype "passive"))
    )
  )
)
